# panel.net
KiCad netlist of a schematic drawn in EAGLE
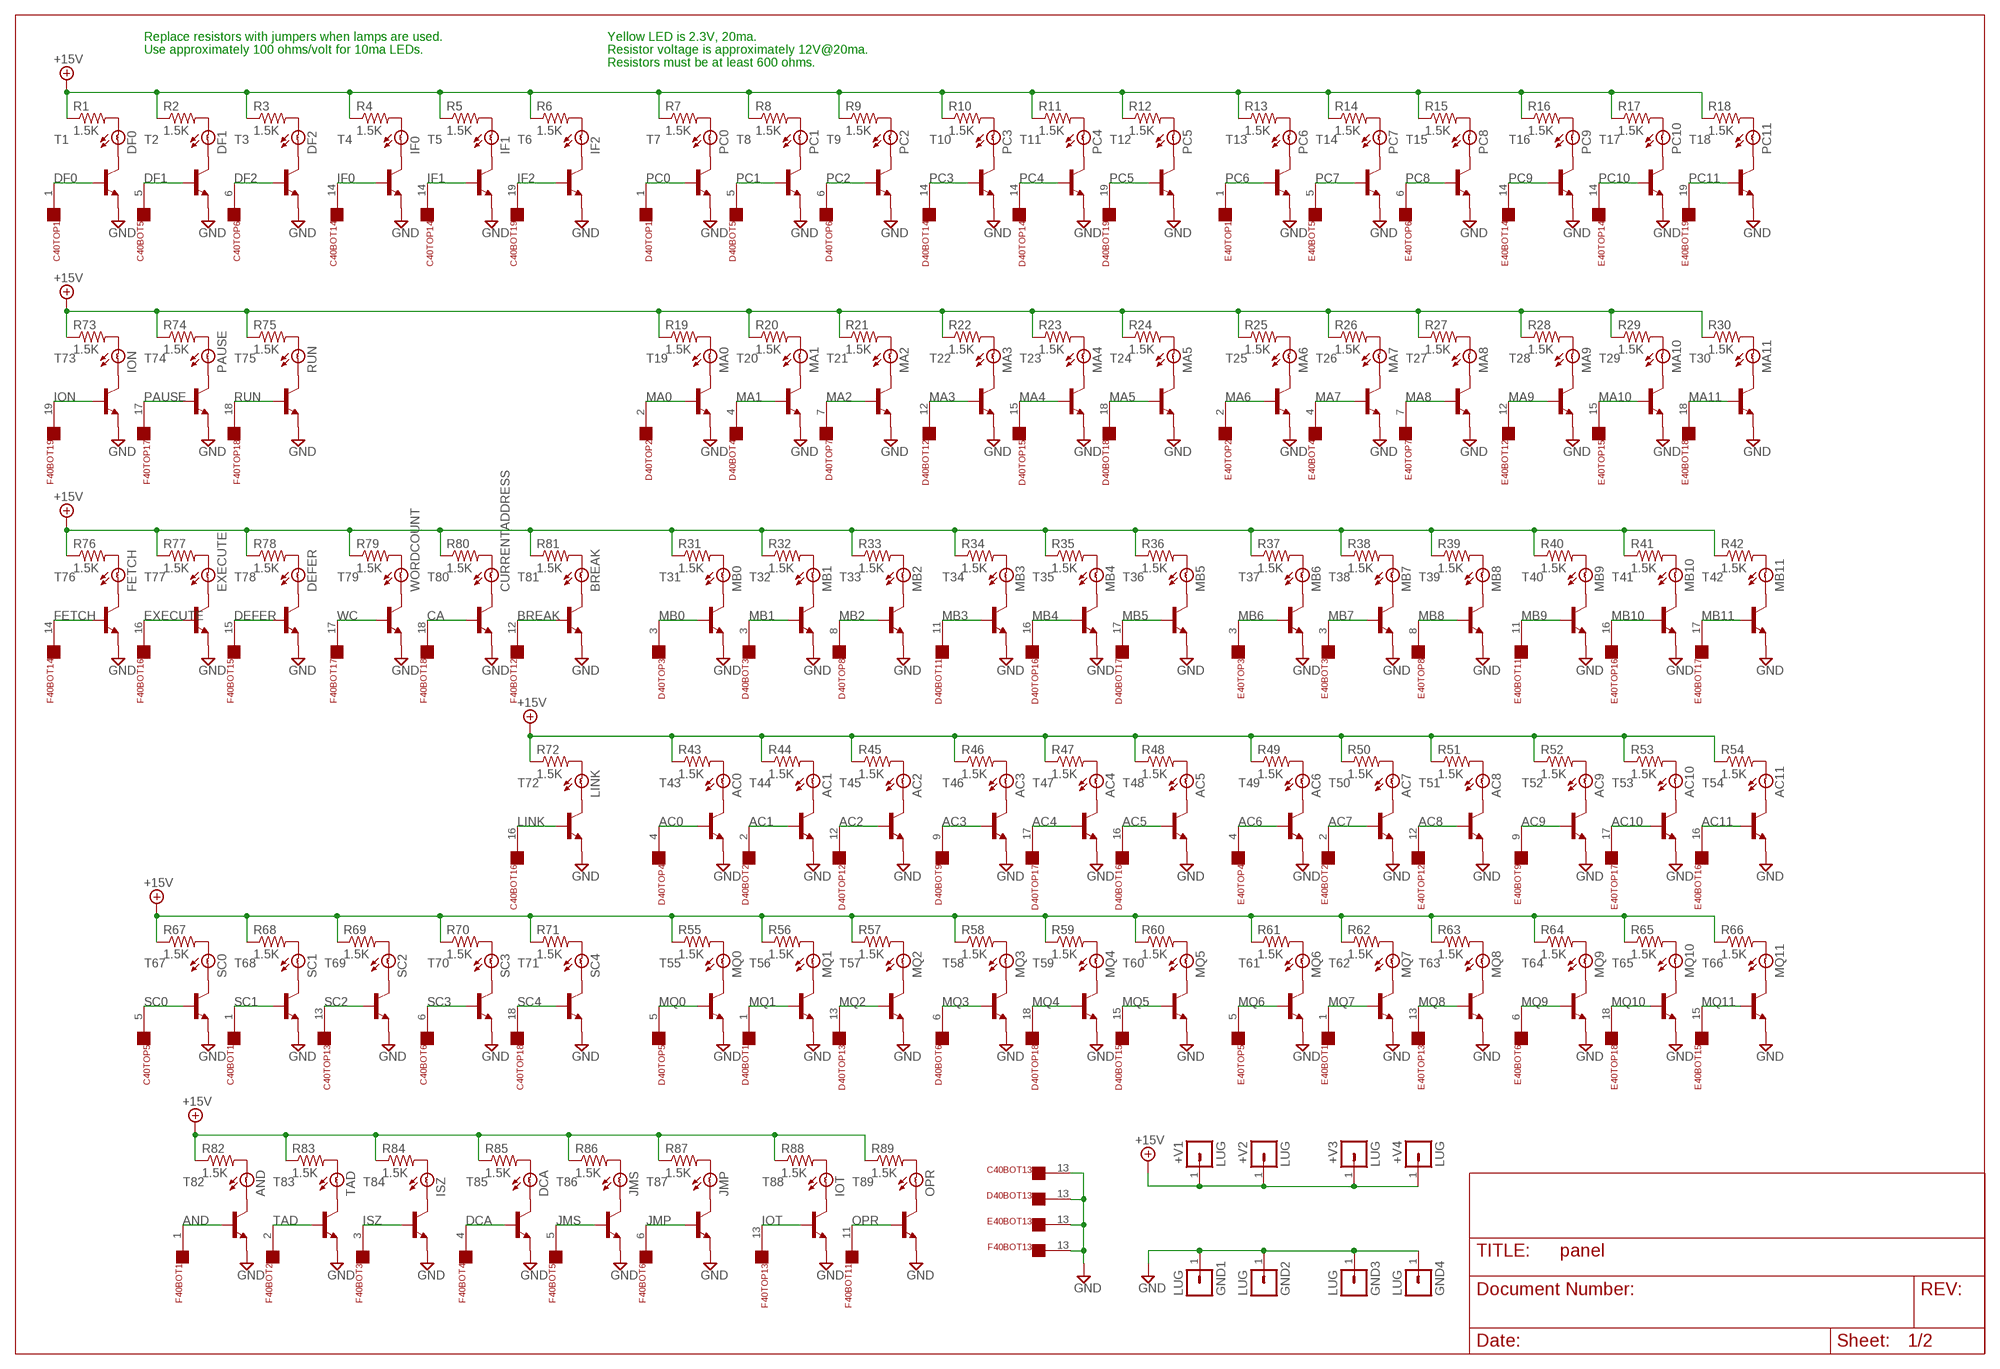
[diagram p0: schematic, sheet 1]
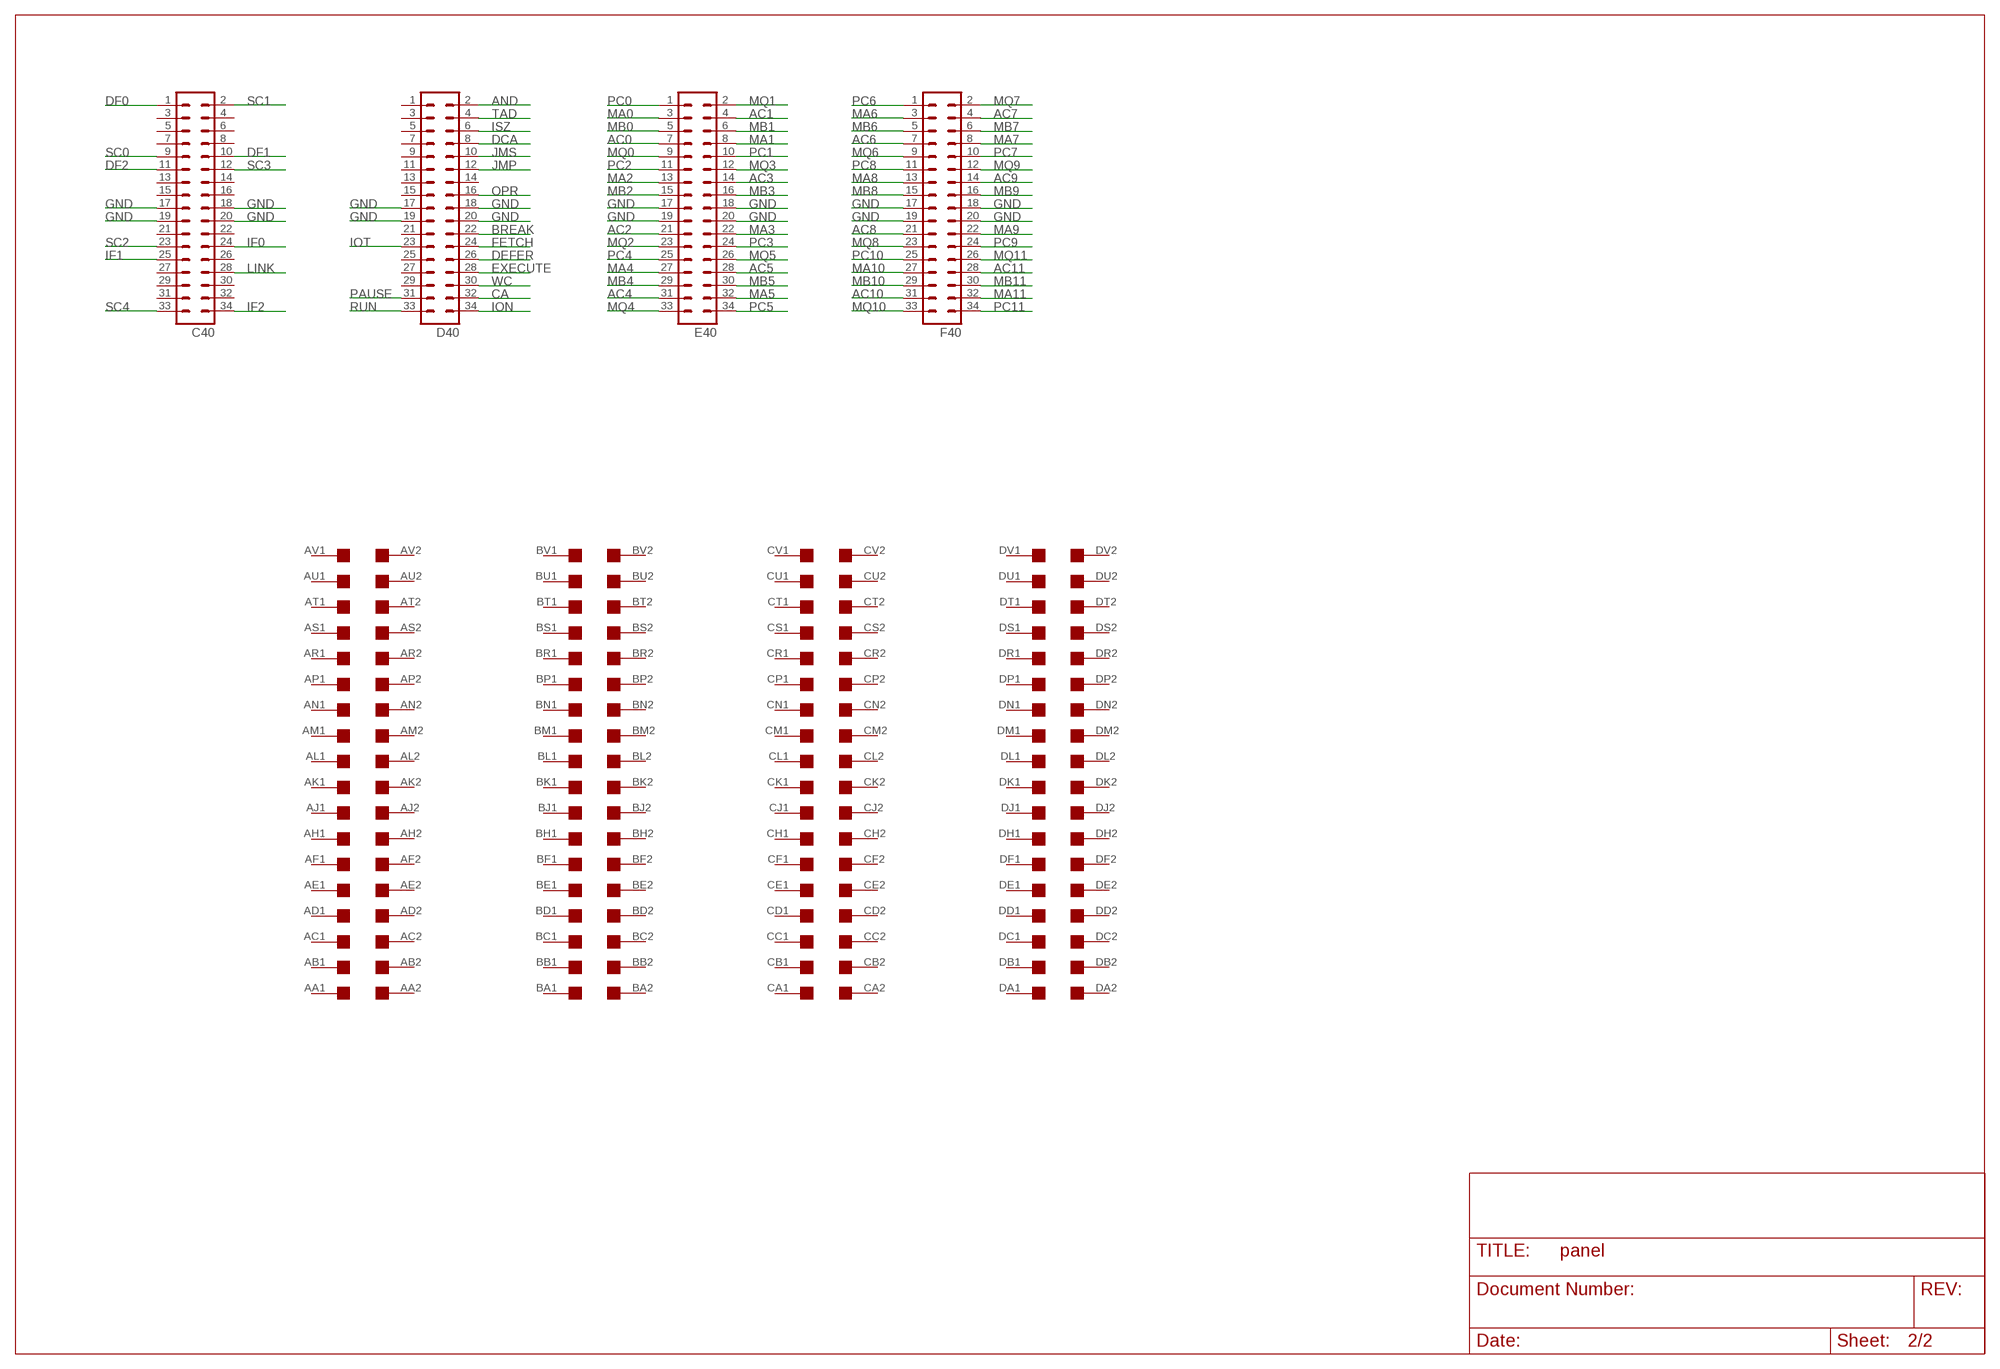
[diagram p1: schematic, sheet 2]

(export (version "E")
  (design (tool "Eeschema 10.0.6"))
  (components
    (comp (ref "+V1")
      (value "LUG")
      (footprint "eagle-import:SPADELUG")
      (libsource (lib "eagle-import") (part "LUG"))
    )
    (comp (ref "+V2")
      (value "LUG")
      (footprint "eagle-import:SPADELUG")
      (libsource (lib "eagle-import") (part "LUG"))
    )
    (comp (ref "+V3")
      (value "LUG")
      (footprint "eagle-import:SPADELUG")
      (libsource (lib "eagle-import") (part "LUG"))
    )
    (comp (ref "+V4")
      (value "LUG")
      (footprint "eagle-import:SPADELUG")
      (libsource (lib "eagle-import") (part "LUG"))
    )
    (comp (ref "AC0")
      (value "BULB")
      (footprint "eagle-import:BULB")
      (libsource (lib "eagle-import") (part "BULB"))
    )
    (comp (ref "AC1")
      (value "BULB")
      (footprint "eagle-import:BULB")
      (libsource (lib "eagle-import") (part "BULB"))
    )
    (comp (ref "AC2")
      (value "BULB")
      (footprint "eagle-import:BULB")
      (libsource (lib "eagle-import") (part "BULB"))
    )
    (comp (ref "AC3")
      (value "BULB")
      (footprint "eagle-import:BULB")
      (libsource (lib "eagle-import") (part "BULB"))
    )
    (comp (ref "AC4")
      (value "BULB")
      (footprint "eagle-import:BULB")
      (libsource (lib "eagle-import") (part "BULB"))
    )
    (comp (ref "AC5")
      (value "BULB")
      (footprint "eagle-import:BULB")
      (libsource (lib "eagle-import") (part "BULB"))
    )
    (comp (ref "AC6")
      (value "BULB")
      (footprint "eagle-import:BULB")
      (libsource (lib "eagle-import") (part "BULB"))
    )
    (comp (ref "AC7")
      (value "BULB")
      (footprint "eagle-import:BULB")
      (libsource (lib "eagle-import") (part "BULB"))
    )
    (comp (ref "AC8")
      (value "BULB")
      (footprint "eagle-import:BULB")
      (libsource (lib "eagle-import") (part "BULB"))
    )
    (comp (ref "AC9")
      (value "BULB")
      (footprint "eagle-import:BULB")
      (libsource (lib "eagle-import") (part "BULB"))
    )
    (comp (ref "AC10")
      (value "BULB")
      (footprint "eagle-import:BULB")
      (libsource (lib "eagle-import") (part "BULB"))
    )
    (comp (ref "AC11")
      (value "BULB")
      (footprint "eagle-import:BULB")
      (libsource (lib "eagle-import") (part "BULB"))
    )
    (comp (ref "AND")
      (value "BULB")
      (footprint "eagle-import:BULB")
      (libsource (lib "eagle-import") (part "BULB"))
    )
    (comp (ref "BREAK")
      (value "BULB")
      (footprint "eagle-import:BULB")
      (libsource (lib "eagle-import") (part "BULB"))
    )
    (comp (ref "C40BOT")
      (value "FLEX19")
      (footprint "eagle-import:FLEX19")
      (libsource (lib "eagle-import") (part "FLEX19"))
    )
    (comp (ref "C40TOP")
      (value "FLEX19")
      (footprint "eagle-import:FLEX19")
      (libsource (lib "eagle-import") (part "FLEX19"))
    )
    (comp (ref "CURRENTADDRESS")
      (value "BULB")
      (footprint "eagle-import:BULB")
      (libsource (lib "eagle-import") (part "BULB"))
    )
    (comp (ref "D40BOT")
      (value "FLEX19")
      (footprint "eagle-import:FLEX19")
      (libsource (lib "eagle-import") (part "FLEX19"))
    )
    (comp (ref "D40TOP")
      (value "FLEX19")
      (footprint "eagle-import:FLEX19")
      (libsource (lib "eagle-import") (part "FLEX19"))
    )
    (comp (ref "DCA")
      (value "BULB")
      (footprint "eagle-import:BULB")
      (libsource (lib "eagle-import") (part "BULB"))
    )
    (comp (ref "DEFER")
      (value "BULB")
      (footprint "eagle-import:BULB")
      (libsource (lib "eagle-import") (part "BULB"))
    )
    (comp (ref "DF0")
      (value "BULB")
      (footprint "eagle-import:BULB")
      (libsource (lib "eagle-import") (part "BULB"))
    )
    (comp (ref "DF1")
      (value "BULB")
      (footprint "eagle-import:BULB")
      (libsource (lib "eagle-import") (part "BULB"))
    )
    (comp (ref "DF2")
      (value "BULB")
      (footprint "eagle-import:BULB")
      (libsource (lib "eagle-import") (part "BULB"))
    )
    (comp (ref "E40BOT")
      (value "FLEX19")
      (footprint "eagle-import:FLEX19")
      (libsource (lib "eagle-import") (part "FLEX19"))
    )
    (comp (ref "E40TOP")
      (value "FLEX19")
      (footprint "eagle-import:FLEX19")
      (libsource (lib "eagle-import") (part "FLEX19"))
    )
    (comp (ref "EXECUTE")
      (value "BULB")
      (footprint "eagle-import:BULB")
      (libsource (lib "eagle-import") (part "BULB"))
    )
    (comp (ref "F40BOT")
      (value "FLEX19")
      (footprint "eagle-import:FLEX19")
      (libsource (lib "eagle-import") (part "FLEX19"))
    )
    (comp (ref "F40TOP")
      (value "FLEX19")
      (footprint "eagle-import:FLEX19")
      (libsource (lib "eagle-import") (part "FLEX19"))
    )
    (comp (ref "FETCH")
      (value "BULB")
      (footprint "eagle-import:BULB")
      (libsource (lib "eagle-import") (part "BULB"))
    )
    (comp (ref "GND1")
      (value "LUG")
      (footprint "eagle-import:SPADELUG")
      (libsource (lib "eagle-import") (part "LUG"))
    )
    (comp (ref "GND2")
      (value "LUG")
      (footprint "eagle-import:SPADELUG")
      (libsource (lib "eagle-import") (part "LUG"))
    )
    (comp (ref "GND3")
      (value "LUG")
      (footprint "eagle-import:SPADELUG")
      (libsource (lib "eagle-import") (part "LUG"))
    )
    (comp (ref "GND4")
      (value "LUG")
      (footprint "eagle-import:SPADELUG")
      (libsource (lib "eagle-import") (part "LUG"))
    )
    (comp (ref "IF0")
      (value "BULB")
      (footprint "eagle-import:BULB")
      (libsource (lib "eagle-import") (part "BULB"))
    )
    (comp (ref "IF1")
      (value "BULB")
      (footprint "eagle-import:BULB")
      (libsource (lib "eagle-import") (part "BULB"))
    )
    (comp (ref "IF2")
      (value "BULB")
      (footprint "eagle-import:BULB")
      (libsource (lib "eagle-import") (part "BULB"))
    )
    (comp (ref "ION")
      (value "BULB")
      (footprint "eagle-import:BULB")
      (libsource (lib "eagle-import") (part "BULB"))
    )
    (comp (ref "IOT")
      (value "BULB")
      (footprint "eagle-import:BULB")
      (libsource (lib "eagle-import") (part "BULB"))
    )
    (comp (ref "ISZ")
      (value "BULB")
      (footprint "eagle-import:BULB")
      (libsource (lib "eagle-import") (part "BULB"))
    )
    (comp (ref "JMP")
      (value "BULB")
      (footprint "eagle-import:BULB")
      (libsource (lib "eagle-import") (part "BULB"))
    )
    (comp (ref "JMS")
      (value "BULB")
      (footprint "eagle-import:BULB")
      (libsource (lib "eagle-import") (part "BULB"))
    )
    (comp (ref "LINK")
      (value "BULB")
      (footprint "eagle-import:BULB")
      (libsource (lib "eagle-import") (part "BULB"))
    )
    (comp (ref "MA0")
      (value "BULB")
      (footprint "eagle-import:BULB")
      (libsource (lib "eagle-import") (part "BULB"))
    )
    (comp (ref "MA1")
      (value "BULB")
      (footprint "eagle-import:BULB")
      (libsource (lib "eagle-import") (part "BULB"))
    )
    (comp (ref "MA2")
      (value "BULB")
      (footprint "eagle-import:BULB")
      (libsource (lib "eagle-import") (part "BULB"))
    )
    (comp (ref "MA3")
      (value "BULB")
      (footprint "eagle-import:BULB")
      (libsource (lib "eagle-import") (part "BULB"))
    )
    (comp (ref "MA4")
      (value "BULB")
      (footprint "eagle-import:BULB")
      (libsource (lib "eagle-import") (part "BULB"))
    )
    (comp (ref "MA5")
      (value "BULB")
      (footprint "eagle-import:BULB")
      (libsource (lib "eagle-import") (part "BULB"))
    )
    (comp (ref "MA6")
      (value "BULB")
      (footprint "eagle-import:BULB")
      (libsource (lib "eagle-import") (part "BULB"))
    )
    (comp (ref "MA7")
      (value "BULB")
      (footprint "eagle-import:BULB")
      (libsource (lib "eagle-import") (part "BULB"))
    )
    (comp (ref "MA8")
      (value "BULB")
      (footprint "eagle-import:BULB")
      (libsource (lib "eagle-import") (part "BULB"))
    )
    (comp (ref "MA9")
      (value "BULB")
      (footprint "eagle-import:BULB")
      (libsource (lib "eagle-import") (part "BULB"))
    )
    (comp (ref "MA10")
      (value "BULB")
      (footprint "eagle-import:BULB")
      (libsource (lib "eagle-import") (part "BULB"))
    )
    (comp (ref "MA11")
      (value "BULB")
      (footprint "eagle-import:BULB")
      (libsource (lib "eagle-import") (part "BULB"))
    )
    (comp (ref "MB0")
      (value "BULB")
      (footprint "eagle-import:BULB")
      (libsource (lib "eagle-import") (part "BULB"))
    )
    (comp (ref "MB1")
      (value "BULB")
      (footprint "eagle-import:BULB")
      (libsource (lib "eagle-import") (part "BULB"))
    )
    (comp (ref "MB2")
      (value "BULB")
      (footprint "eagle-import:BULB")
      (libsource (lib "eagle-import") (part "BULB"))
    )
    (comp (ref "MB3")
      (value "BULB")
      (footprint "eagle-import:BULB")
      (libsource (lib "eagle-import") (part "BULB"))
    )
    (comp (ref "MB4")
      (value "BULB")
      (footprint "eagle-import:BULB")
      (libsource (lib "eagle-import") (part "BULB"))
    )
    (comp (ref "MB5")
      (value "BULB")
      (footprint "eagle-import:BULB")
      (libsource (lib "eagle-import") (part "BULB"))
    )
    (comp (ref "MB6")
      (value "BULB")
      (footprint "eagle-import:BULB")
      (libsource (lib "eagle-import") (part "BULB"))
    )
    (comp (ref "MB7")
      (value "BULB")
      (footprint "eagle-import:BULB")
      (libsource (lib "eagle-import") (part "BULB"))
    )
    (comp (ref "MB8")
      (value "BULB")
      (footprint "eagle-import:BULB")
      (libsource (lib "eagle-import") (part "BULB"))
    )
    (comp (ref "MB9")
      (value "BULB")
      (footprint "eagle-import:BULB")
      (libsource (lib "eagle-import") (part "BULB"))
    )
    (comp (ref "MB10")
      (value "BULB")
      (footprint "eagle-import:BULB")
      (libsource (lib "eagle-import") (part "BULB"))
    )
    (comp (ref "MB11")
      (value "BULB")
      (footprint "eagle-import:BULB")
      (libsource (lib "eagle-import") (part "BULB"))
    )
    (comp (ref "MQ0")
      (value "BULB")
      (footprint "eagle-import:BULB")
      (libsource (lib "eagle-import") (part "BULB"))
    )
    (comp (ref "MQ1")
      (value "BULB")
      (footprint "eagle-import:BULB")
      (libsource (lib "eagle-import") (part "BULB"))
    )
    (comp (ref "MQ2")
      (value "BULB")
      (footprint "eagle-import:BULB")
      (libsource (lib "eagle-import") (part "BULB"))
    )
    (comp (ref "MQ3")
      (value "BULB")
      (footprint "eagle-import:BULB")
      (libsource (lib "eagle-import") (part "BULB"))
    )
    (comp (ref "MQ4")
      (value "BULB")
      (footprint "eagle-import:BULB")
      (libsource (lib "eagle-import") (part "BULB"))
    )
    (comp (ref "MQ5")
      (value "BULB")
      (footprint "eagle-import:BULB")
      (libsource (lib "eagle-import") (part "BULB"))
    )
    (comp (ref "MQ6")
      (value "BULB")
      (footprint "eagle-import:BULB")
      (libsource (lib "eagle-import") (part "BULB"))
    )
    (comp (ref "MQ7")
      (value "BULB")
      (footprint "eagle-import:BULB")
      (libsource (lib "eagle-import") (part "BULB"))
    )
    (comp (ref "MQ8")
      (value "BULB")
      (footprint "eagle-import:BULB")
      (libsource (lib "eagle-import") (part "BULB"))
    )
    (comp (ref "MQ9")
      (value "BULB")
      (footprint "eagle-import:BULB")
      (libsource (lib "eagle-import") (part "BULB"))
    )
    (comp (ref "MQ10")
      (value "BULB")
      (footprint "eagle-import:BULB")
      (libsource (lib "eagle-import") (part "BULB"))
    )
    (comp (ref "MQ11")
      (value "BULB")
      (footprint "eagle-import:BULB")
      (libsource (lib "eagle-import") (part "BULB"))
    )
    (comp (ref "OPR")
      (value "BULB")
      (footprint "eagle-import:BULB")
      (libsource (lib "eagle-import") (part "BULB"))
    )
    (comp (ref "PAUSE")
      (value "BULB")
      (footprint "eagle-import:BULB")
      (libsource (lib "eagle-import") (part "BULB"))
    )
    (comp (ref "PC0")
      (value "BULB")
      (footprint "eagle-import:BULB")
      (libsource (lib "eagle-import") (part "BULB"))
    )
    (comp (ref "PC1")
      (value "BULB")
      (footprint "eagle-import:BULB")
      (libsource (lib "eagle-import") (part "BULB"))
    )
    (comp (ref "PC2")
      (value "BULB")
      (footprint "eagle-import:BULB")
      (libsource (lib "eagle-import") (part "BULB"))
    )
    (comp (ref "PC3")
      (value "BULB")
      (footprint "eagle-import:BULB")
      (libsource (lib "eagle-import") (part "BULB"))
    )
    (comp (ref "PC4")
      (value "BULB")
      (footprint "eagle-import:BULB")
      (libsource (lib "eagle-import") (part "BULB"))
    )
    (comp (ref "PC5")
      (value "BULB")
      (footprint "eagle-import:BULB")
      (libsource (lib "eagle-import") (part "BULB"))
    )
    (comp (ref "PC6")
      (value "BULB")
      (footprint "eagle-import:BULB")
      (libsource (lib "eagle-import") (part "BULB"))
    )
    (comp (ref "PC7")
      (value "BULB")
      (footprint "eagle-import:BULB")
      (libsource (lib "eagle-import") (part "BULB"))
    )
    (comp (ref "PC8")
      (value "BULB")
      (footprint "eagle-import:BULB")
      (libsource (lib "eagle-import") (part "BULB"))
    )
    (comp (ref "PC9")
      (value "BULB")
      (footprint "eagle-import:BULB")
      (libsource (lib "eagle-import") (part "BULB"))
    )
    (comp (ref "PC10")
      (value "BULB")
      (footprint "eagle-import:BULB")
      (libsource (lib "eagle-import") (part "BULB"))
    )
    (comp (ref "PC11")
      (value "BULB")
      (footprint "eagle-import:BULB")
      (libsource (lib "eagle-import") (part "BULB"))
    )
    (comp (ref "R1")
      (value "1.5K")
      (footprint "eagle-import:0207_10")
      (libsource (lib "eagle-import") (part "R-US_0207/10"))
    )
    (comp (ref "R2")
      (value "1.5K")
      (footprint "eagle-import:0207_10")
      (libsource (lib "eagle-import") (part "R-US_0207/10"))
    )
    (comp (ref "R3")
      (value "1.5K")
      (footprint "eagle-import:0207_10")
      (libsource (lib "eagle-import") (part "R-US_0207/10"))
    )
    (comp (ref "R4")
      (value "1.5K")
      (footprint "eagle-import:0207_10")
      (libsource (lib "eagle-import") (part "R-US_0207/10"))
    )
    (comp (ref "R5")
      (value "1.5K")
      (footprint "eagle-import:0207_10")
      (libsource (lib "eagle-import") (part "R-US_0207/10"))
    )
    (comp (ref "R6")
      (value "1.5K")
      (footprint "eagle-import:0207_10")
      (libsource (lib "eagle-import") (part "R-US_0207/10"))
    )
    (comp (ref "R7")
      (value "1.5K")
      (footprint "eagle-import:0207_10")
      (libsource (lib "eagle-import") (part "R-US_0207/10"))
    )
    (comp (ref "R8")
      (value "1.5K")
      (footprint "eagle-import:0207_10")
      (libsource (lib "eagle-import") (part "R-US_0207/10"))
    )
    (comp (ref "R9")
      (value "1.5K")
      (footprint "eagle-import:0207_10")
      (libsource (lib "eagle-import") (part "R-US_0207/10"))
    )
    (comp (ref "R10")
      (value "1.5K")
      (footprint "eagle-import:0207_10")
      (libsource (lib "eagle-import") (part "R-US_0207/10"))
    )
    (comp (ref "R11")
      (value "1.5K")
      (footprint "eagle-import:0207_10")
      (libsource (lib "eagle-import") (part "R-US_0207/10"))
    )
    (comp (ref "R12")
      (value "1.5K")
      (footprint "eagle-import:0207_10")
      (libsource (lib "eagle-import") (part "R-US_0207/10"))
    )
    (comp (ref "R13")
      (value "1.5K")
      (footprint "eagle-import:0207_10")
      (libsource (lib "eagle-import") (part "R-US_0207/10"))
    )
    (comp (ref "R14")
      (value "1.5K")
      (footprint "eagle-import:0207_10")
      (libsource (lib "eagle-import") (part "R-US_0207/10"))
    )
    (comp (ref "R15")
      (value "1.5K")
      (footprint "eagle-import:0207_10")
      (libsource (lib "eagle-import") (part "R-US_0207/10"))
    )
    (comp (ref "R16")
      (value "1.5K")
      (footprint "eagle-import:0207_10")
      (libsource (lib "eagle-import") (part "R-US_0207/10"))
    )
    (comp (ref "R17")
      (value "1.5K")
      (footprint "eagle-import:0207_10")
      (libsource (lib "eagle-import") (part "R-US_0207/10"))
    )
    (comp (ref "R18")
      (value "1.5K")
      (footprint "eagle-import:0207_10")
      (libsource (lib "eagle-import") (part "R-US_0207/10"))
    )
    (comp (ref "R19")
      (value "1.5K")
      (footprint "eagle-import:0207_10")
      (libsource (lib "eagle-import") (part "R-US_0207/10"))
    )
    (comp (ref "R20")
      (value "1.5K")
      (footprint "eagle-import:0207_10")
      (libsource (lib "eagle-import") (part "R-US_0207/10"))
    )
    (comp (ref "R21")
      (value "1.5K")
      (footprint "eagle-import:0207_10")
      (libsource (lib "eagle-import") (part "R-US_0207/10"))
    )
    (comp (ref "R22")
      (value "1.5K")
      (footprint "eagle-import:0207_10")
      (libsource (lib "eagle-import") (part "R-US_0207/10"))
    )
    (comp (ref "R23")
      (value "1.5K")
      (footprint "eagle-import:0207_10")
      (libsource (lib "eagle-import") (part "R-US_0207/10"))
    )
    (comp (ref "R24")
      (value "1.5K")
      (footprint "eagle-import:0207_10")
      (libsource (lib "eagle-import") (part "R-US_0207/10"))
    )
    (comp (ref "R25")
      (value "1.5K")
      (footprint "eagle-import:0207_10")
      (libsource (lib "eagle-import") (part "R-US_0207/10"))
    )
    (comp (ref "R26")
      (value "1.5K")
      (footprint "eagle-import:0207_10")
      (libsource (lib "eagle-import") (part "R-US_0207/10"))
    )
    (comp (ref "R27")
      (value "1.5K")
      (footprint "eagle-import:0207_10")
      (libsource (lib "eagle-import") (part "R-US_0207/10"))
    )
    (comp (ref "R28")
      (value "1.5K")
      (footprint "eagle-import:0207_10")
      (libsource (lib "eagle-import") (part "R-US_0207/10"))
    )
    (comp (ref "R29")
      (value "1.5K")
      (footprint "eagle-import:0207_10")
      (libsource (lib "eagle-import") (part "R-US_0207/10"))
    )
    (comp (ref "R30")
      (value "1.5K")
      (footprint "eagle-import:0207_10")
      (libsource (lib "eagle-import") (part "R-US_0207/10"))
    )
    (comp (ref "R31")
      (value "1.5K")
      (footprint "eagle-import:0207_10")
      (libsource (lib "eagle-import") (part "R-US_0207/10"))
    )
    (comp (ref "R32")
      (value "1.5K")
      (footprint "eagle-import:0207_10")
      (libsource (lib "eagle-import") (part "R-US_0207/10"))
    )
    (comp (ref "R33")
      (value "1.5K")
      (footprint "eagle-import:0207_10")
      (libsource (lib "eagle-import") (part "R-US_0207/10"))
    )
    (comp (ref "R34")
      (value "1.5K")
      (footprint "eagle-import:0207_10")
      (libsource (lib "eagle-import") (part "R-US_0207/10"))
    )
    (comp (ref "R35")
      (value "1.5K")
      (footprint "eagle-import:0207_10")
      (libsource (lib "eagle-import") (part "R-US_0207/10"))
    )
    (comp (ref "R36")
      (value "1.5K")
      (footprint "eagle-import:0207_10")
      (libsource (lib "eagle-import") (part "R-US_0207/10"))
    )
    (comp (ref "R37")
      (value "1.5K")
      (footprint "eagle-import:0207_10")
      (libsource (lib "eagle-import") (part "R-US_0207/10"))
    )
    (comp (ref "R38")
      (value "1.5K")
      (footprint "eagle-import:0207_10")
      (libsource (lib "eagle-import") (part "R-US_0207/10"))
    )
    (comp (ref "R39")
      (value "1.5K")
      (footprint "eagle-import:0207_10")
      (libsource (lib "eagle-import") (part "R-US_0207/10"))
    )
    (comp (ref "R40")
      (value "1.5K")
      (footprint "eagle-import:0207_10")
      (libsource (lib "eagle-import") (part "R-US_0207/10"))
    )
    (comp (ref "R41")
      (value "1.5K")
      (footprint "eagle-import:0207_10")
      (libsource (lib "eagle-import") (part "R-US_0207/10"))
    )
    (comp (ref "R42")
      (value "1.5K")
      (footprint "eagle-import:0207_10")
      (libsource (lib "eagle-import") (part "R-US_0207/10"))
    )
    (comp (ref "R43")
      (value "1.5K")
      (footprint "eagle-import:0207_10")
      (libsource (lib "eagle-import") (part "R-US_0207/10"))
    )
    (comp (ref "R44")
      (value "1.5K")
      (footprint "eagle-import:0207_10")
      (libsource (lib "eagle-import") (part "R-US_0207/10"))
    )
    (comp (ref "R45")
      (value "1.5K")
      (footprint "eagle-import:0207_10")
      (libsource (lib "eagle-import") (part "R-US_0207/10"))
    )
    (comp (ref "R46")
      (value "1.5K")
      (footprint "eagle-import:0207_10")
      (libsource (lib "eagle-import") (part "R-US_0207/10"))
    )
    (comp (ref "R47")
      (value "1.5K")
      (footprint "eagle-import:0207_10")
      (libsource (lib "eagle-import") (part "R-US_0207/10"))
    )
    (comp (ref "R48")
      (value "1.5K")
      (footprint "eagle-import:0207_10")
      (libsource (lib "eagle-import") (part "R-US_0207/10"))
    )
    (comp (ref "R49")
      (value "1.5K")
      (footprint "eagle-import:0207_10")
      (libsource (lib "eagle-import") (part "R-US_0207/10"))
    )
    (comp (ref "R50")
      (value "1.5K")
      (footprint "eagle-import:0207_10")
      (libsource (lib "eagle-import") (part "R-US_0207/10"))
    )
    (comp (ref "R51")
      (value "1.5K")
      (footprint "eagle-import:0207_10")
      (libsource (lib "eagle-import") (part "R-US_0207/10"))
    )
    (comp (ref "R52")
      (value "1.5K")
      (footprint "eagle-import:0207_10")
      (libsource (lib "eagle-import") (part "R-US_0207/10"))
    )
    (comp (ref "R53")
      (value "1.5K")
      (footprint "eagle-import:0207_10")
      (libsource (lib "eagle-import") (part "R-US_0207/10"))
    )
    (comp (ref "R54")
      (value "1.5K")
      (footprint "eagle-import:0207_10")
      (libsource (lib "eagle-import") (part "R-US_0207/10"))
    )
    (comp (ref "R55")
      (value "1.5K")
      (footprint "eagle-import:0207_10")
      (libsource (lib "eagle-import") (part "R-US_0207/10"))
    )
    (comp (ref "R56")
      (value "1.5K")
      (footprint "eagle-import:0207_10")
      (libsource (lib "eagle-import") (part "R-US_0207/10"))
    )
    (comp (ref "R57")
      (value "1.5K")
      (footprint "eagle-import:0207_10")
      (libsource (lib "eagle-import") (part "R-US_0207/10"))
    )
    (comp (ref "R58")
      (value "1.5K")
      (footprint "eagle-import:0207_10")
      (libsource (lib "eagle-import") (part "R-US_0207/10"))
    )
    (comp (ref "R59")
      (value "1.5K")
      (footprint "eagle-import:0207_10")
      (libsource (lib "eagle-import") (part "R-US_0207/10"))
    )
    (comp (ref "R60")
      (value "1.5K")
      (footprint "eagle-import:0207_10")
      (libsource (lib "eagle-import") (part "R-US_0207/10"))
    )
    (comp (ref "R61")
      (value "1.5K")
      (footprint "eagle-import:0207_10")
      (libsource (lib "eagle-import") (part "R-US_0207/10"))
    )
    (comp (ref "R62")
      (value "1.5K")
      (footprint "eagle-import:0207_10")
      (libsource (lib "eagle-import") (part "R-US_0207/10"))
    )
    (comp (ref "R63")
      (value "1.5K")
      (footprint "eagle-import:0207_10")
      (libsource (lib "eagle-import") (part "R-US_0207/10"))
    )
    (comp (ref "R64")
      (value "1.5K")
      (footprint "eagle-import:0207_10")
      (libsource (lib "eagle-import") (part "R-US_0207/10"))
    )
    (comp (ref "R65")
      (value "1.5K")
      (footprint "eagle-import:0207_10")
      (libsource (lib "eagle-import") (part "R-US_0207/10"))
    )
    (comp (ref "R66")
      (value "1.5K")
      (footprint "eagle-import:0207_10")
      (libsource (lib "eagle-import") (part "R-US_0207/10"))
    )
    (comp (ref "R67")
      (value "1.5K")
      (footprint "eagle-import:0207_10")
      (libsource (lib "eagle-import") (part "R-US_0207/10"))
    )
    (comp (ref "R68")
      (value "1.5K")
      (footprint "eagle-import:0207_10")
      (libsource (lib "eagle-import") (part "R-US_0207/10"))
    )
    (comp (ref "R69")
      (value "1.5K")
      (footprint "eagle-import:0207_10")
      (libsource (lib "eagle-import") (part "R-US_0207/10"))
    )
    (comp (ref "R70")
      (value "1.5K")
      (footprint "eagle-import:0207_10")
      (libsource (lib "eagle-import") (part "R-US_0207/10"))
    )
    (comp (ref "R71")
      (value "1.5K")
      (footprint "eagle-import:0207_10")
      (libsource (lib "eagle-import") (part "R-US_0207/10"))
    )
    (comp (ref "R72")
      (value "1.5K")
      (footprint "eagle-import:0207_10")
      (libsource (lib "eagle-import") (part "R-US_0207/10"))
    )
    (comp (ref "R73")
      (value "1.5K")
      (footprint "eagle-import:0207_10")
      (libsource (lib "eagle-import") (part "R-US_0207/10"))
    )
    (comp (ref "R74")
      (value "1.5K")
      (footprint "eagle-import:0207_10")
      (libsource (lib "eagle-import") (part "R-US_0207/10"))
    )
    (comp (ref "R75")
      (value "1.5K")
      (footprint "eagle-import:0207_10")
      (libsource (lib "eagle-import") (part "R-US_0207/10"))
    )
    (comp (ref "R76")
      (value "1.5K")
      (footprint "eagle-import:0207_10")
      (libsource (lib "eagle-import") (part "R-US_0207/10"))
    )
    (comp (ref "R77")
      (value "1.5K")
      (footprint "eagle-import:0207_10")
      (libsource (lib "eagle-import") (part "R-US_0207/10"))
    )
    (comp (ref "R78")
      (value "1.5K")
      (footprint "eagle-import:0207_10")
      (libsource (lib "eagle-import") (part "R-US_0207/10"))
    )
    (comp (ref "R79")
      (value "1.5K")
      (footprint "eagle-import:0207_10")
      (libsource (lib "eagle-import") (part "R-US_0207/10"))
    )
    (comp (ref "R80")
      (value "1.5K")
      (footprint "eagle-import:0207_10")
      (libsource (lib "eagle-import") (part "R-US_0207/10"))
    )
    (comp (ref "R81")
      (value "1.5K")
      (footprint "eagle-import:0207_10")
      (libsource (lib "eagle-import") (part "R-US_0207/10"))
    )
    (comp (ref "R82")
      (value "1.5K")
      (footprint "eagle-import:0207_10")
      (libsource (lib "eagle-import") (part "R-US_0207/10"))
    )
    (comp (ref "R83")
      (value "1.5K")
      (footprint "eagle-import:0207_10")
      (libsource (lib "eagle-import") (part "R-US_0207/10"))
    )
    (comp (ref "R84")
      (value "1.5K")
      (footprint "eagle-import:0207_10")
      (libsource (lib "eagle-import") (part "R-US_0207/10"))
    )
    (comp (ref "R85")
      (value "1.5K")
      (footprint "eagle-import:0207_10")
      (libsource (lib "eagle-import") (part "R-US_0207/10"))
    )
    (comp (ref "R86")
      (value "1.5K")
      (footprint "eagle-import:0207_10")
      (libsource (lib "eagle-import") (part "R-US_0207/10"))
    )
    (comp (ref "R87")
      (value "1.5K")
      (footprint "eagle-import:0207_10")
      (libsource (lib "eagle-import") (part "R-US_0207/10"))
    )
    (comp (ref "R88")
      (value "1.5K")
      (footprint "eagle-import:0207_10")
      (libsource (lib "eagle-import") (part "R-US_0207/10"))
    )
    (comp (ref "R89")
      (value "1.5K")
      (footprint "eagle-import:0207_10")
      (libsource (lib "eagle-import") (part "R-US_0207/10"))
    )
    (comp (ref "RUN")
      (value "BULB")
      (footprint "eagle-import:BULB")
      (libsource (lib "eagle-import") (part "BULB"))
    )
    (comp (ref "SC0")
      (value "BULB")
      (footprint "eagle-import:BULB")
      (libsource (lib "eagle-import") (part "BULB"))
    )
    (comp (ref "SC1")
      (value "BULB")
      (footprint "eagle-import:BULB")
      (libsource (lib "eagle-import") (part "BULB"))
    )
    (comp (ref "SC2")
      (value "BULB")
      (footprint "eagle-import:BULB")
      (libsource (lib "eagle-import") (part "BULB"))
    )
    (comp (ref "SC3")
      (value "BULB")
      (footprint "eagle-import:BULB")
      (libsource (lib "eagle-import") (part "BULB"))
    )
    (comp (ref "SC4")
      (value "BULB")
      (footprint "eagle-import:BULB")
      (libsource (lib "eagle-import") (part "BULB"))
    )
    (comp (ref "T1")
      (value "MPS2222A-NPN-TO92-CBE")
      (footprint "eagle-import:TO92-CBE")
      (libsource (lib "eagle-import") (part "-NPN-TO92-CBEMPS2222A"))
    )
    (comp (ref "T2")
      (value "MPS2222A-NPN-TO92-CBE")
      (footprint "eagle-import:TO92-CBE")
      (libsource (lib "eagle-import") (part "-NPN-TO92-CBEMPS2222A"))
    )
    (comp (ref "T3")
      (value "MPS2222A-NPN-TO92-CBE")
      (footprint "eagle-import:TO92-CBE")
      (libsource (lib "eagle-import") (part "-NPN-TO92-CBEMPS2222A"))
    )
    (comp (ref "T4")
      (value "MPS2222A-NPN-TO92-CBE")
      (footprint "eagle-import:TO92-CBE")
      (libsource (lib "eagle-import") (part "-NPN-TO92-CBEMPS2222A"))
    )
    (comp (ref "T5")
      (value "MPS2222A-NPN-TO92-CBE")
      (footprint "eagle-import:TO92-CBE")
      (libsource (lib "eagle-import") (part "-NPN-TO92-CBEMPS2222A"))
    )
    (comp (ref "T6")
      (value "MPS2222A-NPN-TO92-CBE")
      (footprint "eagle-import:TO92-CBE")
      (libsource (lib "eagle-import") (part "-NPN-TO92-CBEMPS2222A"))
    )
    (comp (ref "T7")
      (value "MPS2222A-NPN-TO92-CBE")
      (footprint "eagle-import:TO92-CBE")
      (libsource (lib "eagle-import") (part "-NPN-TO92-CBEMPS2222A"))
    )
    (comp (ref "T8")
      (value "MPS2222A-NPN-TO92-CBE")
      (footprint "eagle-import:TO92-CBE")
      (libsource (lib "eagle-import") (part "-NPN-TO92-CBEMPS2222A"))
    )
    (comp (ref "T9")
      (value "MPS2222A-NPN-TO92-CBE")
      (footprint "eagle-import:TO92-CBE")
      (libsource (lib "eagle-import") (part "-NPN-TO92-CBEMPS2222A"))
    )
    (comp (ref "T10")
      (value "MPS2222A-NPN-TO92-CBE")
      (footprint "eagle-import:TO92-CBE")
      (libsource (lib "eagle-import") (part "-NPN-TO92-CBEMPS2222A"))
    )
    (comp (ref "T11")
      (value "MPS2222A-NPN-TO92-CBE")
      (footprint "eagle-import:TO92-CBE")
      (libsource (lib "eagle-import") (part "-NPN-TO92-CBEMPS2222A"))
    )
    (comp (ref "T12")
      (value "MPS2222A-NPN-TO92-CBE")
      (footprint "eagle-import:TO92-CBE")
      (libsource (lib "eagle-import") (part "-NPN-TO92-CBEMPS2222A"))
    )
    (comp (ref "T13")
      (value "MPS2222A-NPN-TO92-CBE")
      (footprint "eagle-import:TO92-CBE")
      (libsource (lib "eagle-import") (part "-NPN-TO92-CBEMPS2222A"))
    )
    (comp (ref "T14")
      (value "MPS2222A-NPN-TO92-CBE")
      (footprint "eagle-import:TO92-CBE")
      (libsource (lib "eagle-import") (part "-NPN-TO92-CBEMPS2222A"))
    )
    (comp (ref "T15")
      (value "MPS2222A-NPN-TO92-CBE")
      (footprint "eagle-import:TO92-CBE")
      (libsource (lib "eagle-import") (part "-NPN-TO92-CBEMPS2222A"))
    )
    (comp (ref "T16")
      (value "MPS2222A-NPN-TO92-CBE")
      (footprint "eagle-import:TO92-CBE")
      (libsource (lib "eagle-import") (part "-NPN-TO92-CBEMPS2222A"))
    )
    (comp (ref "T17")
      (value "MPS2222A-NPN-TO92-CBE")
      (footprint "eagle-import:TO92-CBE")
      (libsource (lib "eagle-import") (part "-NPN-TO92-CBEMPS2222A"))
    )
    (comp (ref "T18")
      (value "MPS2222A-NPN-TO92-CBE")
      (footprint "eagle-import:TO92-CBE")
      (libsource (lib "eagle-import") (part "-NPN-TO92-CBEMPS2222A"))
    )
    (comp (ref "T19")
      (value "MPS2222A-NPN-TO92-CBE")
      (footprint "eagle-import:TO92-CBE")
      (libsource (lib "eagle-import") (part "-NPN-TO92-CBEMPS2222A"))
    )
    (comp (ref "T20")
      (value "MPS2222A-NPN-TO92-CBE")
      (footprint "eagle-import:TO92-CBE")
      (libsource (lib "eagle-import") (part "-NPN-TO92-CBEMPS2222A"))
    )
    (comp (ref "T21")
      (value "MPS2222A-NPN-TO92-CBE")
      (footprint "eagle-import:TO92-CBE")
      (libsource (lib "eagle-import") (part "-NPN-TO92-CBEMPS2222A"))
    )
    (comp (ref "T22")
      (value "MPS2222A-NPN-TO92-CBE")
      (footprint "eagle-import:TO92-CBE")
      (libsource (lib "eagle-import") (part "-NPN-TO92-CBEMPS2222A"))
    )
    (comp (ref "T23")
      (value "MPS2222A-NPN-TO92-CBE")
      (footprint "eagle-import:TO92-CBE")
      (libsource (lib "eagle-import") (part "-NPN-TO92-CBEMPS2222A"))
    )
    (comp (ref "T24")
      (value "MPS2222A-NPN-TO92-CBE")
      (footprint "eagle-import:TO92-CBE")
      (libsource (lib "eagle-import") (part "-NPN-TO92-CBEMPS2222A"))
    )
    (comp (ref "T25")
      (value "MPS2222A-NPN-TO92-CBE")
      (footprint "eagle-import:TO92-CBE")
      (libsource (lib "eagle-import") (part "-NPN-TO92-CBEMPS2222A"))
    )
    (comp (ref "T26")
      (value "MPS2222A-NPN-TO92-CBE")
      (footprint "eagle-import:TO92-CBE")
      (libsource (lib "eagle-import") (part "-NPN-TO92-CBEMPS2222A"))
    )
    (comp (ref "T27")
      (value "MPS2222A-NPN-TO92-CBE")
      (footprint "eagle-import:TO92-CBE")
      (libsource (lib "eagle-import") (part "-NPN-TO92-CBEMPS2222A"))
    )
    (comp (ref "T28")
      (value "MPS2222A-NPN-TO92-CBE")
      (footprint "eagle-import:TO92-CBE")
      (libsource (lib "eagle-import") (part "-NPN-TO92-CBEMPS2222A"))
    )
    (comp (ref "T29")
      (value "MPS2222A-NPN-TO92-CBE")
      (footprint "eagle-import:TO92-CBE")
      (libsource (lib "eagle-import") (part "-NPN-TO92-CBEMPS2222A"))
    )
    (comp (ref "T30")
      (value "MPS2222A-NPN-TO92-CBE")
      (footprint "eagle-import:TO92-CBE")
      (libsource (lib "eagle-import") (part "-NPN-TO92-CBEMPS2222A"))
    )
    (comp (ref "T31")
      (value "MPS2222A-NPN-TO92-CBE")
      (footprint "eagle-import:TO92-CBE")
      (libsource (lib "eagle-import") (part "-NPN-TO92-CBEMPS2222A"))
    )
    (comp (ref "T32")
      (value "MPS2222A-NPN-TO92-CBE")
      (footprint "eagle-import:TO92-CBE")
      (libsource (lib "eagle-import") (part "-NPN-TO92-CBEMPS2222A"))
    )
    (comp (ref "T33")
      (value "MPS2222A-NPN-TO92-CBE")
      (footprint "eagle-import:TO92-CBE")
      (libsource (lib "eagle-import") (part "-NPN-TO92-CBEMPS2222A"))
    )
    (comp (ref "T34")
      (value "MPS2222A-NPN-TO92-CBE")
      (footprint "eagle-import:TO92-CBE")
      (libsource (lib "eagle-import") (part "-NPN-TO92-CBEMPS2222A"))
    )
    (comp (ref "T35")
      (value "MPS2222A-NPN-TO92-CBE")
      (footprint "eagle-import:TO92-CBE")
      (libsource (lib "eagle-import") (part "-NPN-TO92-CBEMPS2222A"))
    )
    (comp (ref "T36")
      (value "MPS2222A-NPN-TO92-CBE")
      (footprint "eagle-import:TO92-CBE")
      (libsource (lib "eagle-import") (part "-NPN-TO92-CBEMPS2222A"))
    )
    (comp (ref "T37")
      (value "MPS2222A-NPN-TO92-CBE")
      (footprint "eagle-import:TO92-CBE")
      (libsource (lib "eagle-import") (part "-NPN-TO92-CBEMPS2222A"))
    )
    (comp (ref "T38")
      (value "MPS2222A-NPN-TO92-CBE")
      (footprint "eagle-import:TO92-CBE")
      (libsource (lib "eagle-import") (part "-NPN-TO92-CBEMPS2222A"))
    )
    (comp (ref "T39")
      (value "MPS2222A-NPN-TO92-CBE")
      (footprint "eagle-import:TO92-CBE")
      (libsource (lib "eagle-import") (part "-NPN-TO92-CBEMPS2222A"))
    )
    (comp (ref "T40")
      (value "MPS2222A-NPN-TO92-CBE")
      (footprint "eagle-import:TO92-CBE")
      (libsource (lib "eagle-import") (part "-NPN-TO92-CBEMPS2222A"))
    )
    (comp (ref "T41")
      (value "MPS2222A-NPN-TO92-CBE")
      (footprint "eagle-import:TO92-CBE")
      (libsource (lib "eagle-import") (part "-NPN-TO92-CBEMPS2222A"))
    )
    (comp (ref "T42")
      (value "MPS2222A-NPN-TO92-CBE")
      (footprint "eagle-import:TO92-CBE")
      (libsource (lib "eagle-import") (part "-NPN-TO92-CBEMPS2222A"))
    )
    (comp (ref "T43")
      (value "MPS2222A-NPN-TO92-CBE")
      (footprint "eagle-import:TO92-CBE")
      (libsource (lib "eagle-import") (part "-NPN-TO92-CBEMPS2222A"))
    )
    (comp (ref "T44")
      (value "MPS2222A-NPN-TO92-CBE")
      (footprint "eagle-import:TO92-CBE")
      (libsource (lib "eagle-import") (part "-NPN-TO92-CBEMPS2222A"))
    )
    (comp (ref "T45")
      (value "MPS2222A-NPN-TO92-CBE")
      (footprint "eagle-import:TO92-CBE")
      (libsource (lib "eagle-import") (part "-NPN-TO92-CBEMPS2222A"))
    )
    (comp (ref "T46")
      (value "MPS2222A-NPN-TO92-CBE")
      (footprint "eagle-import:TO92-CBE")
      (libsource (lib "eagle-import") (part "-NPN-TO92-CBEMPS2222A"))
    )
    (comp (ref "T47")
      (value "MPS2222A-NPN-TO92-CBE")
      (footprint "eagle-import:TO92-CBE")
      (libsource (lib "eagle-import") (part "-NPN-TO92-CBEMPS2222A"))
    )
    (comp (ref "T48")
      (value "MPS2222A-NPN-TO92-CBE")
      (footprint "eagle-import:TO92-CBE")
      (libsource (lib "eagle-import") (part "-NPN-TO92-CBEMPS2222A"))
    )
    (comp (ref "T49")
      (value "MPS2222A-NPN-TO92-CBE")
      (footprint "eagle-import:TO92-CBE")
      (libsource (lib "eagle-import") (part "-NPN-TO92-CBEMPS2222A"))
    )
    (comp (ref "T50")
      (value "MPS2222A-NPN-TO92-CBE")
      (footprint "eagle-import:TO92-CBE")
      (libsource (lib "eagle-import") (part "-NPN-TO92-CBEMPS2222A"))
    )
    (comp (ref "T51")
      (value "MPS2222A-NPN-TO92-CBE")
      (footprint "eagle-import:TO92-CBE")
      (libsource (lib "eagle-import") (part "-NPN-TO92-CBEMPS2222A"))
    )
    (comp (ref "T52")
      (value "MPS2222A-NPN-TO92-CBE")
      (footprint "eagle-import:TO92-CBE")
      (libsource (lib "eagle-import") (part "-NPN-TO92-CBEMPS2222A"))
    )
    (comp (ref "T53")
      (value "MPS2222A-NPN-TO92-CBE")
      (footprint "eagle-import:TO92-CBE")
      (libsource (lib "eagle-import") (part "-NPN-TO92-CBEMPS2222A"))
    )
    (comp (ref "T54")
      (value "MPS2222A-NPN-TO92-CBE")
      (footprint "eagle-import:TO92-CBE")
      (libsource (lib "eagle-import") (part "-NPN-TO92-CBEMPS2222A"))
    )
    (comp (ref "T55")
      (value "MPS2222A-NPN-TO92-CBE")
      (footprint "eagle-import:TO92-CBE")
      (libsource (lib "eagle-import") (part "-NPN-TO92-CBEMPS2222A"))
    )
    (comp (ref "T56")
      (value "MPS2222A-NPN-TO92-CBE")
      (footprint "eagle-import:TO92-CBE")
      (libsource (lib "eagle-import") (part "-NPN-TO92-CBEMPS2222A"))
    )
    (comp (ref "T57")
      (value "MPS2222A-NPN-TO92-CBE")
      (footprint "eagle-import:TO92-CBE")
      (libsource (lib "eagle-import") (part "-NPN-TO92-CBEMPS2222A"))
    )
    (comp (ref "T58")
      (value "MPS2222A-NPN-TO92-CBE")
      (footprint "eagle-import:TO92-CBE")
      (libsource (lib "eagle-import") (part "-NPN-TO92-CBEMPS2222A"))
    )
    (comp (ref "T59")
      (value "MPS2222A-NPN-TO92-CBE")
      (footprint "eagle-import:TO92-CBE")
      (libsource (lib "eagle-import") (part "-NPN-TO92-CBEMPS2222A"))
    )
    (comp (ref "T60")
      (value "MPS2222A-NPN-TO92-CBE")
      (footprint "eagle-import:TO92-CBE")
      (libsource (lib "eagle-import") (part "-NPN-TO92-CBEMPS2222A"))
    )
    (comp (ref "T61")
      (value "MPS2222A-NPN-TO92-CBE")
      (footprint "eagle-import:TO92-CBE")
      (libsource (lib "eagle-import") (part "-NPN-TO92-CBEMPS2222A"))
    )
    (comp (ref "T62")
      (value "MPS2222A-NPN-TO92-CBE")
      (footprint "eagle-import:TO92-CBE")
      (libsource (lib "eagle-import") (part "-NPN-TO92-CBEMPS2222A"))
    )
    (comp (ref "T63")
      (value "MPS2222A-NPN-TO92-CBE")
      (footprint "eagle-import:TO92-CBE")
      (libsource (lib "eagle-import") (part "-NPN-TO92-CBEMPS2222A"))
    )
    (comp (ref "T64")
      (value "MPS2222A-NPN-TO92-CBE")
      (footprint "eagle-import:TO92-CBE")
      (libsource (lib "eagle-import") (part "-NPN-TO92-CBEMPS2222A"))
    )
    (comp (ref "T65")
      (value "MPS2222A-NPN-TO92-CBE")
      (footprint "eagle-import:TO92-CBE")
      (libsource (lib "eagle-import") (part "-NPN-TO92-CBEMPS2222A"))
    )
    (comp (ref "T66")
      (value "MPS2222A-NPN-TO92-CBE")
      (footprint "eagle-import:TO92-CBE")
      (libsource (lib "eagle-import") (part "-NPN-TO92-CBEMPS2222A"))
    )
    (comp (ref "T67")
      (value "MPS2222A-NPN-TO92-CBE")
      (footprint "eagle-import:TO92-CBE")
      (libsource (lib "eagle-import") (part "-NPN-TO92-CBEMPS2222A"))
    )
    (comp (ref "T68")
      (value "MPS2222A-NPN-TO92-CBE")
      (footprint "eagle-import:TO92-CBE")
      (libsource (lib "eagle-import") (part "-NPN-TO92-CBEMPS2222A"))
    )
    (comp (ref "T69")
      (value "MPS2222A-NPN-TO92-CBE")
      (footprint "eagle-import:TO92-CBE")
      (libsource (lib "eagle-import") (part "-NPN-TO92-CBEMPS2222A"))
    )
    (comp (ref "T70")
      (value "MPS2222A-NPN-TO92-CBE")
      (footprint "eagle-import:TO92-CBE")
      (libsource (lib "eagle-import") (part "-NPN-TO92-CBEMPS2222A"))
    )
    (comp (ref "T71")
      (value "MPS2222A-NPN-TO92-CBE")
      (footprint "eagle-import:TO92-CBE")
      (libsource (lib "eagle-import") (part "-NPN-TO92-CBEMPS2222A"))
    )
    (comp (ref "T72")
      (value "MPS2222A-NPN-TO92-CBE")
      (footprint "eagle-import:TO92-CBE")
      (libsource (lib "eagle-import") (part "-NPN-TO92-CBEMPS2222A"))
    )
    (comp (ref "T73")
      (value "MPS2222A-NPN-TO92-CBE")
      (footprint "eagle-import:TO92-CBE")
      (libsource (lib "eagle-import") (part "-NPN-TO92-CBEMPS2222A"))
    )
    (comp (ref "T74")
      (value "MPS2222A-NPN-TO92-CBE")
      (footprint "eagle-import:TO92-CBE")
      (libsource (lib "eagle-import") (part "-NPN-TO92-CBEMPS2222A"))
    )
    (comp (ref "T75")
      (value "MPS2222A-NPN-TO92-CBE")
      (footprint "eagle-import:TO92-CBE")
      (libsource (lib "eagle-import") (part "-NPN-TO92-CBEMPS2222A"))
    )
    (comp (ref "T76")
      (value "MPS2222A-NPN-TO92-CBE")
      (footprint "eagle-import:TO92-CBE")
      (libsource (lib "eagle-import") (part "-NPN-TO92-CBEMPS2222A"))
    )
    (comp (ref "T77")
      (value "MPS2222A-NPN-TO92-CBE")
      (footprint "eagle-import:TO92-CBE")
      (libsource (lib "eagle-import") (part "-NPN-TO92-CBEMPS2222A"))
    )
    (comp (ref "T78")
      (value "MPS2222A-NPN-TO92-CBE")
      (footprint "eagle-import:TO92-CBE")
      (libsource (lib "eagle-import") (part "-NPN-TO92-CBEMPS2222A"))
    )
    (comp (ref "T79")
      (value "MPS2222A-NPN-TO92-CBE")
      (footprint "eagle-import:TO92-CBE")
      (libsource (lib "eagle-import") (part "-NPN-TO92-CBEMPS2222A"))
    )
    (comp (ref "T80")
      (value "MPS2222A-NPN-TO92-CBE")
      (footprint "eagle-import:TO92-CBE")
      (libsource (lib "eagle-import") (part "-NPN-TO92-CBEMPS2222A"))
    )
    (comp (ref "T81")
      (value "MPS2222A-NPN-TO92-CBE")
      (footprint "eagle-import:TO92-CBE")
      (libsource (lib "eagle-import") (part "-NPN-TO92-CBEMPS2222A"))
    )
    (comp (ref "T82")
      (value "MPS2222A-NPN-TO92-CBE")
      (footprint "eagle-import:TO92-CBE")
      (libsource (lib "eagle-import") (part "-NPN-TO92-CBEMPS2222A"))
    )
    (comp (ref "T83")
      (value "MPS2222A-NPN-TO92-CBE")
      (footprint "eagle-import:TO92-CBE")
      (libsource (lib "eagle-import") (part "-NPN-TO92-CBEMPS2222A"))
    )
    (comp (ref "T84")
      (value "MPS2222A-NPN-TO92-CBE")
      (footprint "eagle-import:TO92-CBE")
      (libsource (lib "eagle-import") (part "-NPN-TO92-CBEMPS2222A"))
    )
    (comp (ref "T85")
      (value "MPS2222A-NPN-TO92-CBE")
      (footprint "eagle-import:TO92-CBE")
      (libsource (lib "eagle-import") (part "-NPN-TO92-CBEMPS2222A"))
    )
    (comp (ref "T86")
      (value "MPS2222A-NPN-TO92-CBE")
      (footprint "eagle-import:TO92-CBE")
      (libsource (lib "eagle-import") (part "-NPN-TO92-CBEMPS2222A"))
    )
    (comp (ref "T87")
      (value "MPS2222A-NPN-TO92-CBE")
      (footprint "eagle-import:TO92-CBE")
      (libsource (lib "eagle-import") (part "-NPN-TO92-CBEMPS2222A"))
    )
    (comp (ref "T88")
      (value "MPS2222A-NPN-TO92-CBE")
      (footprint "eagle-import:TO92-CBE")
      (libsource (lib "eagle-import") (part "-NPN-TO92-CBEMPS2222A"))
    )
    (comp (ref "T89")
      (value "MPS2222A-NPN-TO92-CBE")
      (footprint "eagle-import:TO92-CBE")
      (libsource (lib "eagle-import") (part "-NPN-TO92-CBEMPS2222A"))
    )
    (comp (ref "TAD")
      (value "BULB")
      (footprint "eagle-import:BULB")
      (libsource (lib "eagle-import") (part "BULB"))
    )
    (comp (ref "WORDCOUNT")
      (value "BULB")
      (footprint "eagle-import:BULB")
      (libsource (lib "eagle-import") (part "BULB"))
    )
    (comp (ref "C40")
      (value "MA17-2")
      (footprint "eagle-import:MA17-2")
      (libsource (lib "eagle-import") (part "MA17-2"))
    )
    (comp (ref "D40")
      (value "MA17-2")
      (footprint "eagle-import:MA17-2")
      (libsource (lib "eagle-import") (part "MA17-2"))
    )
    (comp (ref "E40")
      (value "MA17-2")
      (footprint "eagle-import:MA17-2")
      (libsource (lib "eagle-import") (part "MA17-2"))
    )
    (comp (ref "F40")
      (value "MA17-2")
      (footprint "eagle-import:MA17-2")
      (libsource (lib "eagle-import") (part "MA17-2"))
    )
    (comp (ref "U$10")
      (value "QUAD")
      (footprint "eagle-import:EDGE-CON8")
      (libsource (lib "eagle-import") (part "QUAD"))
    )
  )
  (nets
    (net (code "1") (name "+15V") (class "Default")
      (node (ref "+V1") (pin "1") (pinfunction "1_1") (pintype "passive"))
      (node (ref "+V2") (pin "1") (pinfunction "1_1") (pintype "passive"))
      (node (ref "+V3") (pin "1") (pinfunction "1_1") (pintype "passive"))
      (node (ref "+V4") (pin "1") (pinfunction "1_1") (pintype "passive"))
      (node (ref "R1") (pin "1") (pinfunction "1_1") (pintype "passive"))
      (node (ref "R10") (pin "1") (pinfunction "1_1") (pintype "passive"))
      (node (ref "R11") (pin "1") (pinfunction "1_1") (pintype "passive"))
      (node (ref "R12") (pin "1") (pinfunction "1_1") (pintype "passive"))
      (node (ref "R13") (pin "1") (pinfunction "1_1") (pintype "passive"))
      (node (ref "R14") (pin "1") (pinfunction "1_1") (pintype "passive"))
      (node (ref "R15") (pin "1") (pinfunction "1_1") (pintype "passive"))
      (node (ref "R16") (pin "1") (pinfunction "1_1") (pintype "passive"))
      (node (ref "R17") (pin "1") (pinfunction "1_1") (pintype "passive"))
      (node (ref "R18") (pin "1") (pinfunction "1_1") (pintype "passive"))
      (node (ref "R19") (pin "1") (pinfunction "1_1") (pintype "passive"))
      (node (ref "R2") (pin "1") (pinfunction "1_1") (pintype "passive"))
      (node (ref "R20") (pin "1") (pinfunction "1_1") (pintype "passive"))
      (node (ref "R21") (pin "1") (pinfunction "1_1") (pintype "passive"))
      (node (ref "R22") (pin "1") (pinfunction "1_1") (pintype "passive"))
      (node (ref "R23") (pin "1") (pinfunction "1_1") (pintype "passive"))
      (node (ref "R24") (pin "1") (pinfunction "1_1") (pintype "passive"))
      (node (ref "R25") (pin "1") (pinfunction "1_1") (pintype "passive"))
      (node (ref "R26") (pin "1") (pinfunction "1_1") (pintype "passive"))
      (node (ref "R27") (pin "1") (pinfunction "1_1") (pintype "passive"))
      (node (ref "R28") (pin "1") (pinfunction "1_1") (pintype "passive"))
      (node (ref "R29") (pin "1") (pinfunction "1_1") (pintype "passive"))
      (node (ref "R3") (pin "1") (pinfunction "1_1") (pintype "passive"))
      (node (ref "R30") (pin "1") (pinfunction "1_1") (pintype "passive"))
      (node (ref "R31") (pin "1") (pinfunction "1_1") (pintype "passive"))
      (node (ref "R32") (pin "1") (pinfunction "1_1") (pintype "passive"))
      (node (ref "R33") (pin "1") (pinfunction "1_1") (pintype "passive"))
      (node (ref "R34") (pin "1") (pinfunction "1_1") (pintype "passive"))
      (node (ref "R35") (pin "1") (pinfunction "1_1") (pintype "passive"))
      (node (ref "R36") (pin "1") (pinfunction "1_1") (pintype "passive"))
      (node (ref "R37") (pin "1") (pinfunction "1_1") (pintype "passive"))
      (node (ref "R38") (pin "1") (pinfunction "1_1") (pintype "passive"))
      (node (ref "R39") (pin "1") (pinfunction "1_1") (pintype "passive"))
      (node (ref "R4") (pin "1") (pinfunction "1_1") (pintype "passive"))
      (node (ref "R40") (pin "1") (pinfunction "1_1") (pintype "passive"))
      (node (ref "R41") (pin "1") (pinfunction "1_1") (pintype "passive"))
      (node (ref "R42") (pin "1") (pinfunction "1_1") (pintype "passive"))
      (node (ref "R43") (pin "1") (pinfunction "1_1") (pintype "passive"))
      (node (ref "R44") (pin "1") (pinfunction "1_1") (pintype "passive"))
      (node (ref "R45") (pin "1") (pinfunction "1_1") (pintype "passive"))
      (node (ref "R46") (pin "1") (pinfunction "1_1") (pintype "passive"))
      (node (ref "R47") (pin "1") (pinfunction "1_1") (pintype "passive"))
      (node (ref "R48") (pin "1") (pinfunction "1_1") (pintype "passive"))
      (node (ref "R49") (pin "1") (pinfunction "1_1") (pintype "passive"))
      (node (ref "R5") (pin "1") (pinfunction "1_1") (pintype "passive"))
      (node (ref "R50") (pin "1") (pinfunction "1_1") (pintype "passive"))
      (node (ref "R51") (pin "1") (pinfunction "1_1") (pintype "passive"))
      (node (ref "R52") (pin "1") (pinfunction "1_1") (pintype "passive"))
      (node (ref "R53") (pin "1") (pinfunction "1_1") (pintype "passive"))
      (node (ref "R54") (pin "1") (pinfunction "1_1") (pintype "passive"))
      (node (ref "R55") (pin "1") (pinfunction "1_1") (pintype "passive"))
      (node (ref "R56") (pin "1") (pinfunction "1_1") (pintype "passive"))
      (node (ref "R57") (pin "1") (pinfunction "1_1") (pintype "passive"))
      (node (ref "R58") (pin "1") (pinfunction "1_1") (pintype "passive"))
      (node (ref "R59") (pin "1") (pinfunction "1_1") (pintype "passive"))
      (node (ref "R6") (pin "1") (pinfunction "1_1") (pintype "passive"))
      (node (ref "R60") (pin "1") (pinfunction "1_1") (pintype "passive"))
      (node (ref "R61") (pin "1") (pinfunction "1_1") (pintype "passive"))
      (node (ref "R62") (pin "1") (pinfunction "1_1") (pintype "passive"))
      (node (ref "R63") (pin "1") (pinfunction "1_1") (pintype "passive"))
      (node (ref "R64") (pin "1") (pinfunction "1_1") (pintype "passive"))
      (node (ref "R65") (pin "1") (pinfunction "1_1") (pintype "passive"))
      (node (ref "R66") (pin "1") (pinfunction "1_1") (pintype "passive"))
      (node (ref "R67") (pin "1") (pinfunction "1_1") (pintype "passive"))
      (node (ref "R68") (pin "1") (pinfunction "1_1") (pintype "passive"))
      (node (ref "R69") (pin "1") (pinfunction "1_1") (pintype "passive"))
      (node (ref "R7") (pin "1") (pinfunction "1_1") (pintype "passive"))
      (node (ref "R70") (pin "1") (pinfunction "1_1") (pintype "passive"))
      (node (ref "R71") (pin "1") (pinfunction "1_1") (pintype "passive"))
      (node (ref "R72") (pin "1") (pinfunction "1_1") (pintype "passive"))
      (node (ref "R73") (pin "1") (pinfunction "1_1") (pintype "passive"))
      (node (ref "R74") (pin "1") (pinfunction "1_1") (pintype "passive"))
      (node (ref "R75") (pin "1") (pinfunction "1_1") (pintype "passive"))
      (node (ref "R76") (pin "1") (pinfunction "1_1") (pintype "passive"))
      (node (ref "R77") (pin "1") (pinfunction "1_1") (pintype "passive"))
      (node (ref "R78") (pin "1") (pinfunction "1_1") (pintype "passive"))
      (node (ref "R79") (pin "1") (pinfunction "1_1") (pintype "passive"))
      (node (ref "R8") (pin "1") (pinfunction "1_1") (pintype "passive"))
      (node (ref "R80") (pin "1") (pinfunction "1_1") (pintype "passive"))
      (node (ref "R81") (pin "1") (pinfunction "1_1") (pintype "passive"))
      (node (ref "R82") (pin "1") (pinfunction "1_1") (pintype "passive"))
      (node (ref "R83") (pin "1") (pinfunction "1_1") (pintype "passive"))
      (node (ref "R84") (pin "1") (pinfunction "1_1") (pintype "passive"))
      (node (ref "R85") (pin "1") (pinfunction "1_1") (pintype "passive"))
      (node (ref "R86") (pin "1") (pinfunction "1_1") (pintype "passive"))
      (node (ref "R87") (pin "1") (pinfunction "1_1") (pintype "passive"))
      (node (ref "R88") (pin "1") (pinfunction "1_1") (pintype "passive"))
      (node (ref "R89") (pin "1") (pinfunction "1_1") (pintype "passive"))
      (node (ref "R9") (pin "1") (pinfunction "1_1") (pintype "passive"))
    )
    (net (code "2") (name "AC0") (class "Default")
      (node (ref "D40TOP") (pin "4") (pinfunction "1_4") (pintype "passive"))
      (node (ref "E40") (pin "7") (pinfunction "7_7") (pintype "passive"))
      (node (ref "T43") (pin "B") (pinfunction "B_B") (pintype "passive"))
    )
    (net (code "3") (name "AC1") (class "Default")
      (node (ref "D40BOT") (pin "2") (pinfunction "1_2") (pintype "passive"))
      (node (ref "E40") (pin "4") (pinfunction "4_4") (pintype "passive"))
      (node (ref "T44") (pin "B") (pinfunction "B_B") (pintype "passive"))
    )
    (net (code "4") (name "AC2") (class "Default")
      (node (ref "D40TOP") (pin "12") (pinfunction "1_12") (pintype "passive"))
      (node (ref "E40") (pin "21") (pinfunction "21_21") (pintype "passive"))
      (node (ref "T45") (pin "B") (pinfunction "B_B") (pintype "passive"))
    )
    (net (code "5") (name "AC3") (class "Default")
      (node (ref "D40BOT") (pin "9") (pinfunction "1_9") (pintype "passive"))
      (node (ref "E40") (pin "14") (pinfunction "14_14") (pintype "passive"))
      (node (ref "T46") (pin "B") (pinfunction "B_B") (pintype "passive"))
    )
    (net (code "6") (name "AC4") (class "Default")
      (node (ref "D40TOP") (pin "17") (pinfunction "1_17") (pintype "passive"))
      (node (ref "E40") (pin "31") (pinfunction "31_31") (pintype "passive"))
      (node (ref "T47") (pin "B") (pinfunction "B_B") (pintype "passive"))
    )
    (net (code "7") (name "AC5") (class "Default")
      (node (ref "D40BOT") (pin "16") (pinfunction "1_16") (pintype "passive"))
      (node (ref "E40") (pin "28") (pinfunction "28_28") (pintype "passive"))
      (node (ref "T48") (pin "B") (pinfunction "B_B") (pintype "passive"))
    )
    (net (code "8") (name "AC6") (class "Default")
      (node (ref "E40TOP") (pin "4") (pinfunction "1_4") (pintype "passive"))
      (node (ref "F40") (pin "7") (pinfunction "7_7") (pintype "passive"))
      (node (ref "T49") (pin "B") (pinfunction "B_B") (pintype "passive"))
    )
    (net (code "9") (name "AC7") (class "Default")
      (node (ref "E40BOT") (pin "2") (pinfunction "1_2") (pintype "passive"))
      (node (ref "F40") (pin "4") (pinfunction "4_4") (pintype "passive"))
      (node (ref "T50") (pin "B") (pinfunction "B_B") (pintype "passive"))
    )
    (net (code "10") (name "AC8") (class "Default")
      (node (ref "E40TOP") (pin "12") (pinfunction "1_12") (pintype "passive"))
      (node (ref "F40") (pin "21") (pinfunction "21_21") (pintype "passive"))
      (node (ref "T51") (pin "B") (pinfunction "B_B") (pintype "passive"))
    )
    (net (code "11") (name "AC9") (class "Default")
      (node (ref "E40BOT") (pin "9") (pinfunction "1_9") (pintype "passive"))
      (node (ref "F40") (pin "14") (pinfunction "14_14") (pintype "passive"))
      (node (ref "T52") (pin "B") (pinfunction "B_B") (pintype "passive"))
    )
    (net (code "12") (name "AC10") (class "Default")
      (node (ref "E40TOP") (pin "17") (pinfunction "1_17") (pintype "passive"))
      (node (ref "F40") (pin "31") (pinfunction "31_31") (pintype "passive"))
      (node (ref "T53") (pin "B") (pinfunction "B_B") (pintype "passive"))
    )
    (net (code "13") (name "AC11") (class "Default")
      (node (ref "E40BOT") (pin "16") (pinfunction "1_16") (pintype "passive"))
      (node (ref "F40") (pin "28") (pinfunction "28_28") (pintype "passive"))
      (node (ref "T54") (pin "B") (pinfunction "B_B") (pintype "passive"))
    )
    (net (code "14") (name "AND") (class "Default")
      (node (ref "D40") (pin "2") (pinfunction "2_2") (pintype "passive"))
      (node (ref "F40BOT") (pin "1") (pinfunction "1_1") (pintype "passive"))
      (node (ref "T82") (pin "B") (pinfunction "B_B") (pintype "passive"))
    )
    (net (code "15") (name "BREAK") (class "Default")
      (node (ref "D40") (pin "22") (pinfunction "22_22") (pintype "passive"))
      (node (ref "F40BOT") (pin "12") (pinfunction "1_12") (pintype "passive"))
      (node (ref "T81") (pin "B") (pinfunction "B_B") (pintype "passive"))
    )
    (net (code "16") (name "CA") (class "Default")
      (node (ref "D40") (pin "32") (pinfunction "32_32") (pintype "passive"))
      (node (ref "F40BOT") (pin "18") (pinfunction "1_18") (pintype "passive"))
      (node (ref "T80") (pin "B") (pinfunction "B_B") (pintype "passive"))
    )
    (net (code "17") (name "DCA") (class "Default")
      (node (ref "D40") (pin "8") (pinfunction "8_8") (pintype "passive"))
      (node (ref "F40BOT") (pin "4") (pinfunction "1_4") (pintype "passive"))
      (node (ref "T85") (pin "B") (pinfunction "B_B") (pintype "passive"))
    )
    (net (code "18") (name "DEFER") (class "Default")
      (node (ref "D40") (pin "26") (pinfunction "26_26") (pintype "passive"))
      (node (ref "F40BOT") (pin "15") (pinfunction "1_15") (pintype "passive"))
      (node (ref "T78") (pin "B") (pinfunction "B_B") (pintype "passive"))
    )
    (net (code "19") (name "DF0") (class "Default")
      (node (ref "C40") (pin "1") (pinfunction "1_1") (pintype "passive"))
      (node (ref "C40TOP") (pin "1") (pinfunction "1_1") (pintype "passive"))
      (node (ref "T1") (pin "B") (pinfunction "B_B") (pintype "passive"))
    )
    (net (code "20") (name "DF1") (class "Default")
      (node (ref "C40") (pin "10") (pinfunction "10_10") (pintype "passive"))
      (node (ref "C40BOT") (pin "5") (pinfunction "1_5") (pintype "passive"))
      (node (ref "T2") (pin "B") (pinfunction "B_B") (pintype "passive"))
    )
    (net (code "21") (name "DF2") (class "Default")
      (node (ref "C40") (pin "11") (pinfunction "11_11") (pintype "passive"))
      (node (ref "C40TOP") (pin "6") (pinfunction "1_6") (pintype "passive"))
      (node (ref "T3") (pin "B") (pinfunction "B_B") (pintype "passive"))
    )
    (net (code "22") (name "EXECUTE") (class "Default")
      (node (ref "D40") (pin "28") (pinfunction "28_28") (pintype "passive"))
      (node (ref "F40BOT") (pin "16") (pinfunction "1_16") (pintype "passive"))
      (node (ref "T77") (pin "B") (pinfunction "B_B") (pintype "passive"))
    )
    (net (code "23") (name "FETCH") (class "Default")
      (node (ref "D40") (pin "24") (pinfunction "24_24") (pintype "passive"))
      (node (ref "F40BOT") (pin "14") (pinfunction "1_14") (pintype "passive"))
      (node (ref "T76") (pin "B") (pinfunction "B_B") (pintype "passive"))
    )
    (net (code "24") (name "GND") (class "Default")
      (node (ref "C40") (pin "17") (pinfunction "17_17") (pintype "passive"))
      (node (ref "C40") (pin "18") (pinfunction "18_18") (pintype "passive"))
      (node (ref "C40") (pin "19") (pinfunction "19_19") (pintype "passive"))
      (node (ref "C40") (pin "20") (pinfunction "20_20") (pintype "passive"))
      (node (ref "C40BOT") (pin "13") (pinfunction "1_13") (pintype "passive"))
      (node (ref "D40") (pin "17") (pinfunction "17_17") (pintype "passive"))
      (node (ref "D40") (pin "18") (pinfunction "18_18") (pintype "passive"))
      (node (ref "D40") (pin "19") (pinfunction "19_19") (pintype "passive"))
      (node (ref "D40") (pin "20") (pinfunction "20_20") (pintype "passive"))
      (node (ref "D40BOT") (pin "13") (pinfunction "1_13") (pintype "passive"))
      (node (ref "E40") (pin "17") (pinfunction "17_17") (pintype "passive"))
      (node (ref "E40") (pin "18") (pinfunction "18_18") (pintype "passive"))
      (node (ref "E40") (pin "19") (pinfunction "19_19") (pintype "passive"))
      (node (ref "E40") (pin "20") (pinfunction "20_20") (pintype "passive"))
      (node (ref "E40BOT") (pin "13") (pinfunction "1_13") (pintype "passive"))
      (node (ref "F40") (pin "17") (pinfunction "17_17") (pintype "passive"))
      (node (ref "F40") (pin "18") (pinfunction "18_18") (pintype "passive"))
      (node (ref "F40") (pin "19") (pinfunction "19_19") (pintype "passive"))
      (node (ref "F40") (pin "20") (pinfunction "20_20") (pintype "passive"))
      (node (ref "F40BOT") (pin "13") (pinfunction "1_13") (pintype "passive"))
      (node (ref "GND1") (pin "1") (pinfunction "1_1") (pintype "passive"))
      (node (ref "GND2") (pin "1") (pinfunction "1_1") (pintype "passive"))
      (node (ref "GND3") (pin "1") (pinfunction "1_1") (pintype "passive"))
      (node (ref "GND4") (pin "1") (pinfunction "1_1") (pintype "passive"))
      (node (ref "T1") (pin "E") (pinfunction "E_E") (pintype "passive"))
      (node (ref "T10") (pin "E") (pinfunction "E_E") (pintype "passive"))
      (node (ref "T11") (pin "E") (pinfunction "E_E") (pintype "passive"))
      (node (ref "T12") (pin "E") (pinfunction "E_E") (pintype "passive"))
      (node (ref "T13") (pin "E") (pinfunction "E_E") (pintype "passive"))
      (node (ref "T14") (pin "E") (pinfunction "E_E") (pintype "passive"))
      (node (ref "T15") (pin "E") (pinfunction "E_E") (pintype "passive"))
      (node (ref "T16") (pin "E") (pinfunction "E_E") (pintype "passive"))
      (node (ref "T17") (pin "E") (pinfunction "E_E") (pintype "passive"))
      (node (ref "T18") (pin "E") (pinfunction "E_E") (pintype "passive"))
      (node (ref "T19") (pin "E") (pinfunction "E_E") (pintype "passive"))
      (node (ref "T2") (pin "E") (pinfunction "E_E") (pintype "passive"))
      (node (ref "T20") (pin "E") (pinfunction "E_E") (pintype "passive"))
      (node (ref "T21") (pin "E") (pinfunction "E_E") (pintype "passive"))
      (node (ref "T22") (pin "E") (pinfunction "E_E") (pintype "passive"))
      (node (ref "T23") (pin "E") (pinfunction "E_E") (pintype "passive"))
      (node (ref "T24") (pin "E") (pinfunction "E_E") (pintype "passive"))
      (node (ref "T25") (pin "E") (pinfunction "E_E") (pintype "passive"))
      (node (ref "T26") (pin "E") (pinfunction "E_E") (pintype "passive"))
      (node (ref "T27") (pin "E") (pinfunction "E_E") (pintype "passive"))
      (node (ref "T28") (pin "E") (pinfunction "E_E") (pintype "passive"))
      (node (ref "T29") (pin "E") (pinfunction "E_E") (pintype "passive"))
      (node (ref "T3") (pin "E") (pinfunction "E_E") (pintype "passive"))
      (node (ref "T30") (pin "E") (pinfunction "E_E") (pintype "passive"))
      (node (ref "T31") (pin "E") (pinfunction "E_E") (pintype "passive"))
      (node (ref "T32") (pin "E") (pinfunction "E_E") (pintype "passive"))
      (node (ref "T33") (pin "E") (pinfunction "E_E") (pintype "passive"))
      (node (ref "T34") (pin "E") (pinfunction "E_E") (pintype "passive"))
      (node (ref "T35") (pin "E") (pinfunction "E_E") (pintype "passive"))
      (node (ref "T36") (pin "E") (pinfunction "E_E") (pintype "passive"))
      (node (ref "T37") (pin "E") (pinfunction "E_E") (pintype "passive"))
      (node (ref "T38") (pin "E") (pinfunction "E_E") (pintype "passive"))
      (node (ref "T39") (pin "E") (pinfunction "E_E") (pintype "passive"))
      (node (ref "T4") (pin "E") (pinfunction "E_E") (pintype "passive"))
      (node (ref "T40") (pin "E") (pinfunction "E_E") (pintype "passive"))
      (node (ref "T41") (pin "E") (pinfunction "E_E") (pintype "passive"))
      (node (ref "T42") (pin "E") (pinfunction "E_E") (pintype "passive"))
      (node (ref "T43") (pin "E") (pinfunction "E_E") (pintype "passive"))
      (node (ref "T44") (pin "E") (pinfunction "E_E") (pintype "passive"))
      (node (ref "T45") (pin "E") (pinfunction "E_E") (pintype "passive"))
      (node (ref "T46") (pin "E") (pinfunction "E_E") (pintype "passive"))
      (node (ref "T47") (pin "E") (pinfunction "E_E") (pintype "passive"))
      (node (ref "T48") (pin "E") (pinfunction "E_E") (pintype "passive"))
      (node (ref "T49") (pin "E") (pinfunction "E_E") (pintype "passive"))
      (node (ref "T5") (pin "E") (pinfunction "E_E") (pintype "passive"))
      (node (ref "T50") (pin "E") (pinfunction "E_E") (pintype "passive"))
      (node (ref "T51") (pin "E") (pinfunction "E_E") (pintype "passive"))
      (node (ref "T52") (pin "E") (pinfunction "E_E") (pintype "passive"))
      (node (ref "T53") (pin "E") (pinfunction "E_E") (pintype "passive"))
      (node (ref "T54") (pin "E") (pinfunction "E_E") (pintype "passive"))
      (node (ref "T55") (pin "E") (pinfunction "E_E") (pintype "passive"))
      (node (ref "T56") (pin "E") (pinfunction "E_E") (pintype "passive"))
      (node (ref "T57") (pin "E") (pinfunction "E_E") (pintype "passive"))
      (node (ref "T58") (pin "E") (pinfunction "E_E") (pintype "passive"))
      (node (ref "T59") (pin "E") (pinfunction "E_E") (pintype "passive"))
      (node (ref "T6") (pin "E") (pinfunction "E_E") (pintype "passive"))
      (node (ref "T60") (pin "E") (pinfunction "E_E") (pintype "passive"))
      (node (ref "T61") (pin "E") (pinfunction "E_E") (pintype "passive"))
      (node (ref "T62") (pin "E") (pinfunction "E_E") (pintype "passive"))
      (node (ref "T63") (pin "E") (pinfunction "E_E") (pintype "passive"))
      (node (ref "T64") (pin "E") (pinfunction "E_E") (pintype "passive"))
      (node (ref "T65") (pin "E") (pinfunction "E_E") (pintype "passive"))
      (node (ref "T66") (pin "E") (pinfunction "E_E") (pintype "passive"))
      (node (ref "T67") (pin "E") (pinfunction "E_E") (pintype "passive"))
      (node (ref "T68") (pin "E") (pinfunction "E_E") (pintype "passive"))
      (node (ref "T69") (pin "E") (pinfunction "E_E") (pintype "passive"))
      (node (ref "T7") (pin "E") (pinfunction "E_E") (pintype "passive"))
      (node (ref "T70") (pin "E") (pinfunction "E_E") (pintype "passive"))
      (node (ref "T71") (pin "E") (pinfunction "E_E") (pintype "passive"))
      (node (ref "T72") (pin "E") (pinfunction "E_E") (pintype "passive"))
      (node (ref "T73") (pin "E") (pinfunction "E_E") (pintype "passive"))
      (node (ref "T74") (pin "E") (pinfunction "E_E") (pintype "passive"))
      (node (ref "T75") (pin "E") (pinfunction "E_E") (pintype "passive"))
      (node (ref "T76") (pin "E") (pinfunction "E_E") (pintype "passive"))
      (node (ref "T77") (pin "E") (pinfunction "E_E") (pintype "passive"))
      (node (ref "T78") (pin "E") (pinfunction "E_E") (pintype "passive"))
      (node (ref "T79") (pin "E") (pinfunction "E_E") (pintype "passive"))
      (node (ref "T8") (pin "E") (pinfunction "E_E") (pintype "passive"))
      (node (ref "T80") (pin "E") (pinfunction "E_E") (pintype "passive"))
      (node (ref "T81") (pin "E") (pinfunction "E_E") (pintype "passive"))
      (node (ref "T82") (pin "E") (pinfunction "E_E") (pintype "passive"))
      (node (ref "T83") (pin "E") (pinfunction "E_E") (pintype "passive"))
      (node (ref "T84") (pin "E") (pinfunction "E_E") (pintype "passive"))
      (node (ref "T85") (pin "E") (pinfunction "E_E") (pintype "passive"))
      (node (ref "T86") (pin "E") (pinfunction "E_E") (pintype "passive"))
      (node (ref "T87") (pin "E") (pinfunction "E_E") (pintype "passive"))
      (node (ref "T88") (pin "E") (pinfunction "E_E") (pintype "passive"))
      (node (ref "T89") (pin "E") (pinfunction "E_E") (pintype "passive"))
      (node (ref "T9") (pin "E") (pinfunction "E_E") (pintype "passive"))
    )
    (net (code "25") (name "IF0") (class "Default")
      (node (ref "C40") (pin "24") (pinfunction "24_24") (pintype "passive"))
      (node (ref "C40BOT") (pin "14") (pinfunction "1_14") (pintype "passive"))
      (node (ref "T4") (pin "B") (pinfunction "B_B") (pintype "passive"))
    )
    (net (code "26") (name "IF1") (class "Default")
      (node (ref "C40") (pin "25") (pinfunction "25_25") (pintype "passive"))
      (node (ref "C40TOP") (pin "14") (pinfunction "1_14") (pintype "passive"))
      (node (ref "T5") (pin "B") (pinfunction "B_B") (pintype "passive"))
    )
    (net (code "27") (name "IF2") (class "Default")
      (node (ref "C40") (pin "34") (pinfunction "34_34") (pintype "passive"))
      (node (ref "C40BOT") (pin "19") (pinfunction "1_19") (pintype "passive"))
      (node (ref "T6") (pin "B") (pinfunction "B_B") (pintype "passive"))
    )
    (net (code "28") (name "ION") (class "Default")
      (node (ref "D40") (pin "34") (pinfunction "34_34") (pintype "passive"))
      (node (ref "F40BOT") (pin "19") (pinfunction "1_19") (pintype "passive"))
      (node (ref "T73") (pin "B") (pinfunction "B_B") (pintype "passive"))
    )
    (net (code "29") (name "IOT") (class "Default")
      (node (ref "D40") (pin "23") (pinfunction "23_23") (pintype "passive"))
      (node (ref "F40TOP") (pin "13") (pinfunction "1_13") (pintype "passive"))
      (node (ref "T88") (pin "B") (pinfunction "B_B") (pintype "passive"))
    )
    (net (code "30") (name "ISZ") (class "Default")
      (node (ref "D40") (pin "6") (pinfunction "6_6") (pintype "passive"))
      (node (ref "F40BOT") (pin "3") (pinfunction "1_3") (pintype "passive"))
      (node (ref "T84") (pin "B") (pinfunction "B_B") (pintype "passive"))
    )
    (net (code "31") (name "JMP") (class "Default")
      (node (ref "D40") (pin "12") (pinfunction "12_12") (pintype "passive"))
      (node (ref "F40BOT") (pin "6") (pinfunction "1_6") (pintype "passive"))
      (node (ref "T87") (pin "B") (pinfunction "B_B") (pintype "passive"))
    )
    (net (code "32") (name "JMS") (class "Default")
      (node (ref "D40") (pin "10") (pinfunction "10_10") (pintype "passive"))
      (node (ref "F40BOT") (pin "5") (pinfunction "1_5") (pintype "passive"))
      (node (ref "T86") (pin "B") (pinfunction "B_B") (pintype "passive"))
    )
    (net (code "33") (name "LINK") (class "Default")
      (node (ref "C40") (pin "28") (pinfunction "28_28") (pintype "passive"))
      (node (ref "C40BOT") (pin "16") (pinfunction "1_16") (pintype "passive"))
      (node (ref "T72") (pin "B") (pinfunction "B_B") (pintype "passive"))
    )
    (net (code "34") (name "MA0") (class "Default")
      (node (ref "D40TOP") (pin "2") (pinfunction "1_2") (pintype "passive"))
      (node (ref "E40") (pin "3") (pinfunction "3_3") (pintype "passive"))
      (node (ref "T19") (pin "B") (pinfunction "B_B") (pintype "passive"))
    )
    (net (code "35") (name "MA1") (class "Default")
      (node (ref "D40BOT") (pin "4") (pinfunction "1_4") (pintype "passive"))
      (node (ref "E40") (pin "8") (pinfunction "8_8") (pintype "passive"))
      (node (ref "T20") (pin "B") (pinfunction "B_B") (pintype "passive"))
    )
    (net (code "36") (name "MA2") (class "Default")
      (node (ref "D40TOP") (pin "7") (pinfunction "1_7") (pintype "passive"))
      (node (ref "E40") (pin "13") (pinfunction "13_13") (pintype "passive"))
      (node (ref "T21") (pin "B") (pinfunction "B_B") (pintype "passive"))
    )
    (net (code "37") (name "MA3") (class "Default")
      (node (ref "D40BOT") (pin "12") (pinfunction "1_12") (pintype "passive"))
      (node (ref "E40") (pin "22") (pinfunction "22_22") (pintype "passive"))
      (node (ref "T22") (pin "B") (pinfunction "B_B") (pintype "passive"))
    )
    (net (code "38") (name "MA4") (class "Default")
      (node (ref "D40TOP") (pin "15") (pinfunction "1_15") (pintype "passive"))
      (node (ref "E40") (pin "27") (pinfunction "27_27") (pintype "passive"))
      (node (ref "T23") (pin "B") (pinfunction "B_B") (pintype "passive"))
    )
    (net (code "39") (name "MA5") (class "Default")
      (node (ref "D40BOT") (pin "18") (pinfunction "1_18") (pintype "passive"))
      (node (ref "E40") (pin "32") (pinfunction "32_32") (pintype "passive"))
      (node (ref "T24") (pin "B") (pinfunction "B_B") (pintype "passive"))
    )
    (net (code "40") (name "MA6") (class "Default")
      (node (ref "E40TOP") (pin "2") (pinfunction "1_2") (pintype "passive"))
      (node (ref "F40") (pin "3") (pinfunction "3_3") (pintype "passive"))
      (node (ref "T25") (pin "B") (pinfunction "B_B") (pintype "passive"))
    )
    (net (code "41") (name "MA7") (class "Default")
      (node (ref "E40BOT") (pin "4") (pinfunction "1_4") (pintype "passive"))
      (node (ref "F40") (pin "8") (pinfunction "8_8") (pintype "passive"))
      (node (ref "T26") (pin "B") (pinfunction "B_B") (pintype "passive"))
    )
    (net (code "42") (name "MA8") (class "Default")
      (node (ref "E40TOP") (pin "7") (pinfunction "1_7") (pintype "passive"))
      (node (ref "F40") (pin "13") (pinfunction "13_13") (pintype "passive"))
      (node (ref "T27") (pin "B") (pinfunction "B_B") (pintype "passive"))
    )
    (net (code "43") (name "MA9") (class "Default")
      (node (ref "E40BOT") (pin "12") (pinfunction "1_12") (pintype "passive"))
      (node (ref "F40") (pin "22") (pinfunction "22_22") (pintype "passive"))
      (node (ref "T28") (pin "B") (pinfunction "B_B") (pintype "passive"))
    )
    (net (code "44") (name "MA10") (class "Default")
      (node (ref "E40TOP") (pin "15") (pinfunction "1_15") (pintype "passive"))
      (node (ref "F40") (pin "27") (pinfunction "27_27") (pintype "passive"))
      (node (ref "T29") (pin "B") (pinfunction "B_B") (pintype "passive"))
    )
    (net (code "45") (name "MA11") (class "Default")
      (node (ref "E40BOT") (pin "18") (pinfunction "1_18") (pintype "passive"))
      (node (ref "F40") (pin "32") (pinfunction "32_32") (pintype "passive"))
      (node (ref "T30") (pin "B") (pinfunction "B_B") (pintype "passive"))
    )
    (net (code "46") (name "MB0") (class "Default")
      (node (ref "D40TOP") (pin "3") (pinfunction "1_3") (pintype "passive"))
      (node (ref "E40") (pin "5") (pinfunction "5_5") (pintype "passive"))
      (node (ref "T31") (pin "B") (pinfunction "B_B") (pintype "passive"))
    )
    (net (code "47") (name "MB1") (class "Default")
      (node (ref "D40BOT") (pin "3") (pinfunction "1_3") (pintype "passive"))
      (node (ref "E40") (pin "6") (pinfunction "6_6") (pintype "passive"))
      (node (ref "T32") (pin "B") (pinfunction "B_B") (pintype "passive"))
    )
    (net (code "48") (name "MB2") (class "Default")
      (node (ref "D40TOP") (pin "8") (pinfunction "1_8") (pintype "passive"))
      (node (ref "E40") (pin "15") (pinfunction "15_15") (pintype "passive"))
      (node (ref "T33") (pin "B") (pinfunction "B_B") (pintype "passive"))
    )
    (net (code "49") (name "MB3") (class "Default")
      (node (ref "D40BOT") (pin "11") (pinfunction "1_11") (pintype "passive"))
      (node (ref "E40") (pin "16") (pinfunction "16_16") (pintype "passive"))
      (node (ref "T34") (pin "B") (pinfunction "B_B") (pintype "passive"))
    )
    (net (code "50") (name "MB4") (class "Default")
      (node (ref "D40TOP") (pin "16") (pinfunction "1_16") (pintype "passive"))
      (node (ref "E40") (pin "29") (pinfunction "29_29") (pintype "passive"))
      (node (ref "T35") (pin "B") (pinfunction "B_B") (pintype "passive"))
    )
    (net (code "51") (name "MB5") (class "Default")
      (node (ref "D40BOT") (pin "17") (pinfunction "1_17") (pintype "passive"))
      (node (ref "E40") (pin "30") (pinfunction "30_30") (pintype "passive"))
      (node (ref "T36") (pin "B") (pinfunction "B_B") (pintype "passive"))
    )
    (net (code "52") (name "MB6") (class "Default")
      (node (ref "E40TOP") (pin "3") (pinfunction "1_3") (pintype "passive"))
      (node (ref "F40") (pin "5") (pinfunction "5_5") (pintype "passive"))
      (node (ref "T37") (pin "B") (pinfunction "B_B") (pintype "passive"))
    )
    (net (code "53") (name "MB7") (class "Default")
      (node (ref "E40BOT") (pin "3") (pinfunction "1_3") (pintype "passive"))
      (node (ref "F40") (pin "6") (pinfunction "6_6") (pintype "passive"))
      (node (ref "T38") (pin "B") (pinfunction "B_B") (pintype "passive"))
    )
    (net (code "54") (name "MB8") (class "Default")
      (node (ref "E40TOP") (pin "8") (pinfunction "1_8") (pintype "passive"))
      (node (ref "F40") (pin "15") (pinfunction "15_15") (pintype "passive"))
      (node (ref "T39") (pin "B") (pinfunction "B_B") (pintype "passive"))
    )
    (net (code "55") (name "MB9") (class "Default")
      (node (ref "E40BOT") (pin "11") (pinfunction "1_11") (pintype "passive"))
      (node (ref "F40") (pin "16") (pinfunction "16_16") (pintype "passive"))
      (node (ref "T40") (pin "B") (pinfunction "B_B") (pintype "passive"))
    )
    (net (code "56") (name "MB10") (class "Default")
      (node (ref "E40TOP") (pin "16") (pinfunction "1_16") (pintype "passive"))
      (node (ref "F40") (pin "29") (pinfunction "29_29") (pintype "passive"))
      (node (ref "T41") (pin "B") (pinfunction "B_B") (pintype "passive"))
    )
    (net (code "57") (name "MB11") (class "Default")
      (node (ref "E40BOT") (pin "17") (pinfunction "1_17") (pintype "passive"))
      (node (ref "F40") (pin "30") (pinfunction "30_30") (pintype "passive"))
      (node (ref "T42") (pin "B") (pinfunction "B_B") (pintype "passive"))
    )
    (net (code "58") (name "MQ0") (class "Default")
      (node (ref "D40TOP") (pin "5") (pinfunction "1_5") (pintype "passive"))
      (node (ref "E40") (pin "9") (pinfunction "9_9") (pintype "passive"))
      (node (ref "T55") (pin "B") (pinfunction "B_B") (pintype "passive"))
    )
    (net (code "59") (name "MQ1") (class "Default")
      (node (ref "D40BOT") (pin "1") (pinfunction "1_1") (pintype "passive"))
      (node (ref "E40") (pin "2") (pinfunction "2_2") (pintype "passive"))
      (node (ref "T56") (pin "B") (pinfunction "B_B") (pintype "passive"))
    )
    (net (code "60") (name "MQ2") (class "Default")
      (node (ref "D40TOP") (pin "13") (pinfunction "1_13") (pintype "passive"))
      (node (ref "E40") (pin "23") (pinfunction "23_23") (pintype "passive"))
      (node (ref "T57") (pin "B") (pinfunction "B_B") (pintype "passive"))
    )
    (net (code "61") (name "MQ3") (class "Default")
      (node (ref "D40BOT") (pin "6") (pinfunction "1_6") (pintype "passive"))
      (node (ref "E40") (pin "12") (pinfunction "12_12") (pintype "passive"))
      (node (ref "T58") (pin "B") (pinfunction "B_B") (pintype "passive"))
    )
    (net (code "62") (name "MQ4") (class "Default")
      (node (ref "D40TOP") (pin "18") (pinfunction "1_18") (pintype "passive"))
      (node (ref "E40") (pin "33") (pinfunction "33_33") (pintype "passive"))
      (node (ref "T59") (pin "B") (pinfunction "B_B") (pintype "passive"))
    )
    (net (code "63") (name "MQ5") (class "Default")
      (node (ref "D40BOT") (pin "15") (pinfunction "1_15") (pintype "passive"))
      (node (ref "E40") (pin "26") (pinfunction "26_26") (pintype "passive"))
      (node (ref "T60") (pin "B") (pinfunction "B_B") (pintype "passive"))
    )
    (net (code "64") (name "MQ6") (class "Default")
      (node (ref "E40TOP") (pin "5") (pinfunction "1_5") (pintype "passive"))
      (node (ref "F40") (pin "9") (pinfunction "9_9") (pintype "passive"))
      (node (ref "T61") (pin "B") (pinfunction "B_B") (pintype "passive"))
    )
    (net (code "65") (name "MQ7") (class "Default")
      (node (ref "E40BOT") (pin "1") (pinfunction "1_1") (pintype "passive"))
      (node (ref "F40") (pin "2") (pinfunction "2_2") (pintype "passive"))
      (node (ref "T62") (pin "B") (pinfunction "B_B") (pintype "passive"))
    )
    (net (code "66") (name "MQ8") (class "Default")
      (node (ref "E40TOP") (pin "13") (pinfunction "1_13") (pintype "passive"))
      (node (ref "F40") (pin "23") (pinfunction "23_23") (pintype "passive"))
      (node (ref "T63") (pin "B") (pinfunction "B_B") (pintype "passive"))
    )
    (net (code "67") (name "MQ9") (class "Default")
      (node (ref "E40BOT") (pin "6") (pinfunction "1_6") (pintype "passive"))
      (node (ref "F40") (pin "12") (pinfunction "12_12") (pintype "passive"))
      (node (ref "T64") (pin "B") (pinfunction "B_B") (pintype "passive"))
    )
    (net (code "68") (name "MQ10") (class "Default")
      (node (ref "E40TOP") (pin "18") (pinfunction "1_18") (pintype "passive"))
      (node (ref "F40") (pin "33") (pinfunction "33_33") (pintype "passive"))
      (node (ref "T65") (pin "B") (pinfunction "B_B") (pintype "passive"))
    )
    (net (code "69") (name "MQ11") (class "Default")
      (node (ref "E40BOT") (pin "15") (pinfunction "1_15") (pintype "passive"))
      (node (ref "F40") (pin "26") (pinfunction "26_26") (pintype "passive"))
      (node (ref "T66") (pin "B") (pinfunction "B_B") (pintype "passive"))
    )
    (net (code "70") (name "Net-(AC0-PadA)") (class "Default")
      (node (ref "AC0") (pin "A") (pinfunction "A_A") (pintype "passive"))
      (node (ref "R43") (pin "2") (pinfunction "2_2") (pintype "passive"))
    )
    (net (code "71") (name "Net-(AC0-PadB)") (class "Default")
      (node (ref "AC0") (pin "B") (pinfunction "B_B") (pintype "passive"))
      (node (ref "T43") (pin "C") (pinfunction "C_C") (pintype "passive"))
    )
    (net (code "72") (name "Net-(AC1-PadA)") (class "Default")
      (node (ref "AC1") (pin "A") (pinfunction "A_A") (pintype "passive"))
      (node (ref "R44") (pin "2") (pinfunction "2_2") (pintype "passive"))
    )
    (net (code "73") (name "Net-(AC1-PadB)") (class "Default")
      (node (ref "AC1") (pin "B") (pinfunction "B_B") (pintype "passive"))
      (node (ref "T44") (pin "C") (pinfunction "C_C") (pintype "passive"))
    )
    (net (code "74") (name "Net-(AC2-PadA)") (class "Default")
      (node (ref "AC2") (pin "A") (pinfunction "A_A") (pintype "passive"))
      (node (ref "R45") (pin "2") (pinfunction "2_2") (pintype "passive"))
    )
    (net (code "75") (name "Net-(AC2-PadB)") (class "Default")
      (node (ref "AC2") (pin "B") (pinfunction "B_B") (pintype "passive"))
      (node (ref "T45") (pin "C") (pinfunction "C_C") (pintype "passive"))
    )
    (net (code "76") (name "Net-(AC3-PadA)") (class "Default")
      (node (ref "AC3") (pin "A") (pinfunction "A_A") (pintype "passive"))
      (node (ref "R46") (pin "2") (pinfunction "2_2") (pintype "passive"))
    )
    (net (code "77") (name "Net-(AC3-PadB)") (class "Default")
      (node (ref "AC3") (pin "B") (pinfunction "B_B") (pintype "passive"))
      (node (ref "T46") (pin "C") (pinfunction "C_C") (pintype "passive"))
    )
    (net (code "78") (name "Net-(AC4-PadA)") (class "Default")
      (node (ref "AC4") (pin "A") (pinfunction "A_A") (pintype "passive"))
      (node (ref "R47") (pin "2") (pinfunction "2_2") (pintype "passive"))
    )
    (net (code "79") (name "Net-(AC4-PadB)") (class "Default")
      (node (ref "AC4") (pin "B") (pinfunction "B_B") (pintype "passive"))
      (node (ref "T47") (pin "C") (pinfunction "C_C") (pintype "passive"))
    )
    (net (code "80") (name "Net-(AC5-PadA)") (class "Default")
      (node (ref "AC5") (pin "A") (pinfunction "A_A") (pintype "passive"))
      (node (ref "R48") (pin "2") (pinfunction "2_2") (pintype "passive"))
    )
    (net (code "81") (name "Net-(AC5-PadB)") (class "Default")
      (node (ref "AC5") (pin "B") (pinfunction "B_B") (pintype "passive"))
      (node (ref "T48") (pin "C") (pinfunction "C_C") (pintype "passive"))
    )
    (net (code "82") (name "Net-(AC6-PadA)") (class "Default")
      (node (ref "AC6") (pin "A") (pinfunction "A_A") (pintype "passive"))
      (node (ref "R49") (pin "2") (pinfunction "2_2") (pintype "passive"))
    )
    (net (code "83") (name "Net-(AC6-PadB)") (class "Default")
      (node (ref "AC6") (pin "B") (pinfunction "B_B") (pintype "passive"))
      (node (ref "T49") (pin "C") (pinfunction "C_C") (pintype "passive"))
    )
    (net (code "84") (name "Net-(AC7-PadA)") (class "Default")
      (node (ref "AC7") (pin "A") (pinfunction "A_A") (pintype "passive"))
      (node (ref "R50") (pin "2") (pinfunction "2_2") (pintype "passive"))
    )
    (net (code "85") (name "Net-(AC7-PadB)") (class "Default")
      (node (ref "AC7") (pin "B") (pinfunction "B_B") (pintype "passive"))
      (node (ref "T50") (pin "C") (pinfunction "C_C") (pintype "passive"))
    )
    (net (code "86") (name "Net-(AC8-PadA)") (class "Default")
      (node (ref "AC8") (pin "A") (pinfunction "A_A") (pintype "passive"))
      (node (ref "R51") (pin "2") (pinfunction "2_2") (pintype "passive"))
    )
    (net (code "87") (name "Net-(AC8-PadB)") (class "Default")
      (node (ref "AC8") (pin "B") (pinfunction "B_B") (pintype "passive"))
      (node (ref "T51") (pin "C") (pinfunction "C_C") (pintype "passive"))
    )
    (net (code "88") (name "Net-(AC9-PadA)") (class "Default")
      (node (ref "AC9") (pin "A") (pinfunction "A_A") (pintype "passive"))
      (node (ref "R52") (pin "2") (pinfunction "2_2") (pintype "passive"))
    )
    (net (code "89") (name "Net-(AC9-PadB)") (class "Default")
      (node (ref "AC9") (pin "B") (pinfunction "B_B") (pintype "passive"))
      (node (ref "T52") (pin "C") (pinfunction "C_C") (pintype "passive"))
    )
    (net (code "90") (name "Net-(AC10-PadA)") (class "Default")
      (node (ref "AC10") (pin "A") (pinfunction "A_A") (pintype "passive"))
      (node (ref "R53") (pin "2") (pinfunction "2_2") (pintype "passive"))
    )
    (net (code "91") (name "Net-(AC10-PadB)") (class "Default")
      (node (ref "AC10") (pin "B") (pinfunction "B_B") (pintype "passive"))
      (node (ref "T53") (pin "C") (pinfunction "C_C") (pintype "passive"))
    )
    (net (code "92") (name "Net-(AC11-PadA)") (class "Default")
      (node (ref "AC11") (pin "A") (pinfunction "A_A") (pintype "passive"))
      (node (ref "R54") (pin "2") (pinfunction "2_2") (pintype "passive"))
    )
    (net (code "93") (name "Net-(AC11-PadB)") (class "Default")
      (node (ref "AC11") (pin "B") (pinfunction "B_B") (pintype "passive"))
      (node (ref "T54") (pin "C") (pinfunction "C_C") (pintype "passive"))
    )
    (net (code "94") (name "Net-(AND-PadA)") (class "Default")
      (node (ref "AND") (pin "A") (pinfunction "A_A") (pintype "passive"))
      (node (ref "R82") (pin "2") (pinfunction "2_2") (pintype "passive"))
    )
    (net (code "95") (name "Net-(AND-PadB)") (class "Default")
      (node (ref "AND") (pin "B") (pinfunction "B_B") (pintype "passive"))
      (node (ref "T82") (pin "C") (pinfunction "C_C") (pintype "passive"))
    )
    (net (code "96") (name "Net-(BREAK-PadA)") (class "Default")
      (node (ref "BREAK") (pin "A") (pinfunction "A_A") (pintype "passive"))
      (node (ref "R81") (pin "2") (pinfunction "2_2") (pintype "passive"))
    )
    (net (code "97") (name "Net-(BREAK-PadB)") (class "Default")
      (node (ref "BREAK") (pin "B") (pinfunction "B_B") (pintype "passive"))
      (node (ref "T81") (pin "C") (pinfunction "C_C") (pintype "passive"))
    )
    (net (code "98") (name "Net-(CURRENTADDRESS-PadA)") (class "Default")
      (node (ref "CURRENTADDRESS") (pin "A") (pinfunction "A_A") (pintype "passive"))
      (node (ref "R80") (pin "2") (pinfunction "2_2") (pintype "passive"))
    )
    (net (code "99") (name "Net-(CURRENTADDRESS-PadB)") (class "Default")
      (node (ref "CURRENTADDRESS") (pin "B") (pinfunction "B_B") (pintype "passive"))
      (node (ref "T80") (pin "C") (pinfunction "C_C") (pintype "passive"))
    )
    (net (code "100") (name "Net-(DCA-PadA)") (class "Default")
      (node (ref "DCA") (pin "A") (pinfunction "A_A") (pintype "passive"))
      (node (ref "R85") (pin "2") (pinfunction "2_2") (pintype "passive"))
    )
    (net (code "101") (name "Net-(DCA-PadB)") (class "Default")
      (node (ref "DCA") (pin "B") (pinfunction "B_B") (pintype "passive"))
      (node (ref "T85") (pin "C") (pinfunction "C_C") (pintype "passive"))
    )
    (net (code "102") (name "Net-(DEFER-PadA)") (class "Default")
      (node (ref "DEFER") (pin "A") (pinfunction "A_A") (pintype "passive"))
      (node (ref "R78") (pin "2") (pinfunction "2_2") (pintype "passive"))
    )
    (net (code "103") (name "Net-(DEFER-PadB)") (class "Default")
      (node (ref "DEFER") (pin "B") (pinfunction "B_B") (pintype "passive"))
      (node (ref "T78") (pin "C") (pinfunction "C_C") (pintype "passive"))
    )
    (net (code "104") (name "Net-(DF0-PadA)") (class "Default")
      (node (ref "DF0") (pin "A") (pinfunction "A_A") (pintype "passive"))
      (node (ref "R1") (pin "2") (pinfunction "2_2") (pintype "passive"))
    )
    (net (code "105") (name "Net-(DF0-PadB)") (class "Default")
      (node (ref "DF0") (pin "B") (pinfunction "B_B") (pintype "passive"))
      (node (ref "T1") (pin "C") (pinfunction "C_C") (pintype "passive"))
    )
    (net (code "106") (name "Net-(DF1-PadA)") (class "Default")
      (node (ref "DF1") (pin "A") (pinfunction "A_A") (pintype "passive"))
      (node (ref "R2") (pin "2") (pinfunction "2_2") (pintype "passive"))
    )
    (net (code "107") (name "Net-(DF1-PadB)") (class "Default")
      (node (ref "DF1") (pin "B") (pinfunction "B_B") (pintype "passive"))
      (node (ref "T2") (pin "C") (pinfunction "C_C") (pintype "passive"))
    )
    (net (code "108") (name "Net-(DF2-PadA)") (class "Default")
      (node (ref "DF2") (pin "A") (pinfunction "A_A") (pintype "passive"))
      (node (ref "R3") (pin "2") (pinfunction "2_2") (pintype "passive"))
    )
    (net (code "109") (name "Net-(DF2-PadB)") (class "Default")
      (node (ref "DF2") (pin "B") (pinfunction "B_B") (pintype "passive"))
      (node (ref "T3") (pin "C") (pinfunction "C_C") (pintype "passive"))
    )
    (net (code "110") (name "Net-(EXECUTE-PadA)") (class "Default")
      (node (ref "EXECUTE") (pin "A") (pinfunction "A_A") (pintype "passive"))
      (node (ref "R77") (pin "2") (pinfunction "2_2") (pintype "passive"))
    )
    (net (code "111") (name "Net-(EXECUTE-PadB)") (class "Default")
      (node (ref "EXECUTE") (pin "B") (pinfunction "B_B") (pintype "passive"))
      (node (ref "T77") (pin "C") (pinfunction "C_C") (pintype "passive"))
    )
    (net (code "112") (name "Net-(FETCH-PadA)") (class "Default")
      (node (ref "FETCH") (pin "A") (pinfunction "A_A") (pintype "passive"))
      (node (ref "R76") (pin "2") (pinfunction "2_2") (pintype "passive"))
    )
    (net (code "113") (name "Net-(FETCH-PadB)") (class "Default")
      (node (ref "FETCH") (pin "B") (pinfunction "B_B") (pintype "passive"))
      (node (ref "T76") (pin "C") (pinfunction "C_C") (pintype "passive"))
    )
    (net (code "114") (name "Net-(IF0-PadA)") (class "Default")
      (node (ref "IF0") (pin "A") (pinfunction "A_A") (pintype "passive"))
      (node (ref "R4") (pin "2") (pinfunction "2_2") (pintype "passive"))
    )
    (net (code "115") (name "Net-(IF0-PadB)") (class "Default")
      (node (ref "IF0") (pin "B") (pinfunction "B_B") (pintype "passive"))
      (node (ref "T4") (pin "C") (pinfunction "C_C") (pintype "passive"))
    )
    (net (code "116") (name "Net-(IF1-PadA)") (class "Default")
      (node (ref "IF1") (pin "A") (pinfunction "A_A") (pintype "passive"))
      (node (ref "R5") (pin "2") (pinfunction "2_2") (pintype "passive"))
    )
    (net (code "117") (name "Net-(IF1-PadB)") (class "Default")
      (node (ref "IF1") (pin "B") (pinfunction "B_B") (pintype "passive"))
      (node (ref "T5") (pin "C") (pinfunction "C_C") (pintype "passive"))
    )
    (net (code "118") (name "Net-(IF2-PadA)") (class "Default")
      (node (ref "IF2") (pin "A") (pinfunction "A_A") (pintype "passive"))
      (node (ref "R6") (pin "2") (pinfunction "2_2") (pintype "passive"))
    )
    (net (code "119") (name "Net-(IF2-PadB)") (class "Default")
      (node (ref "IF2") (pin "B") (pinfunction "B_B") (pintype "passive"))
      (node (ref "T6") (pin "C") (pinfunction "C_C") (pintype "passive"))
    )
    (net (code "120") (name "Net-(ION-PadA)") (class "Default")
      (node (ref "ION") (pin "A") (pinfunction "A_A") (pintype "passive"))
      (node (ref "R73") (pin "2") (pinfunction "2_2") (pintype "passive"))
    )
    (net (code "121") (name "Net-(ION-PadB)") (class "Default")
      (node (ref "ION") (pin "B") (pinfunction "B_B") (pintype "passive"))
      (node (ref "T73") (pin "C") (pinfunction "C_C") (pintype "passive"))
    )
    (net (code "122") (name "Net-(IOT-PadA)") (class "Default")
      (node (ref "IOT") (pin "A") (pinfunction "A_A") (pintype "passive"))
      (node (ref "R88") (pin "2") (pinfunction "2_2") (pintype "passive"))
    )
    (net (code "123") (name "Net-(IOT-PadB)") (class "Default")
      (node (ref "IOT") (pin "B") (pinfunction "B_B") (pintype "passive"))
      (node (ref "T88") (pin "C") (pinfunction "C_C") (pintype "passive"))
    )
    (net (code "124") (name "Net-(ISZ-PadA)") (class "Default")
      (node (ref "ISZ") (pin "A") (pinfunction "A_A") (pintype "passive"))
      (node (ref "R84") (pin "2") (pinfunction "2_2") (pintype "passive"))
    )
    (net (code "125") (name "Net-(ISZ-PadB)") (class "Default")
      (node (ref "ISZ") (pin "B") (pinfunction "B_B") (pintype "passive"))
      (node (ref "T84") (pin "C") (pinfunction "C_C") (pintype "passive"))
    )
    (net (code "126") (name "Net-(JMP-PadA)") (class "Default")
      (node (ref "JMP") (pin "A") (pinfunction "A_A") (pintype "passive"))
      (node (ref "R87") (pin "2") (pinfunction "2_2") (pintype "passive"))
    )
    (net (code "127") (name "Net-(JMP-PadB)") (class "Default")
      (node (ref "JMP") (pin "B") (pinfunction "B_B") (pintype "passive"))
      (node (ref "T87") (pin "C") (pinfunction "C_C") (pintype "passive"))
    )
    (net (code "128") (name "Net-(JMS-PadA)") (class "Default")
      (node (ref "JMS") (pin "A") (pinfunction "A_A") (pintype "passive"))
      (node (ref "R86") (pin "2") (pinfunction "2_2") (pintype "passive"))
    )
    (net (code "129") (name "Net-(JMS-PadB)") (class "Default")
      (node (ref "JMS") (pin "B") (pinfunction "B_B") (pintype "passive"))
      (node (ref "T86") (pin "C") (pinfunction "C_C") (pintype "passive"))
    )
    (net (code "130") (name "Net-(LINK-PadA)") (class "Default")
      (node (ref "LINK") (pin "A") (pinfunction "A_A") (pintype "passive"))
      (node (ref "R72") (pin "2") (pinfunction "2_2") (pintype "passive"))
    )
    (net (code "131") (name "Net-(LINK-PadB)") (class "Default")
      (node (ref "LINK") (pin "B") (pinfunction "B_B") (pintype "passive"))
      (node (ref "T72") (pin "C") (pinfunction "C_C") (pintype "passive"))
    )
    (net (code "132") (name "Net-(MA0-PadA)") (class "Default")
      (node (ref "MA0") (pin "A") (pinfunction "A_A") (pintype "passive"))
      (node (ref "R19") (pin "2") (pinfunction "2_2") (pintype "passive"))
    )
    (net (code "133") (name "Net-(MA0-PadB)") (class "Default")
      (node (ref "MA0") (pin "B") (pinfunction "B_B") (pintype "passive"))
      (node (ref "T19") (pin "C") (pinfunction "C_C") (pintype "passive"))
    )
    (net (code "134") (name "Net-(MA1-PadA)") (class "Default")
      (node (ref "MA1") (pin "A") (pinfunction "A_A") (pintype "passive"))
      (node (ref "R20") (pin "2") (pinfunction "2_2") (pintype "passive"))
    )
    (net (code "135") (name "Net-(MA1-PadB)") (class "Default")
      (node (ref "MA1") (pin "B") (pinfunction "B_B") (pintype "passive"))
      (node (ref "T20") (pin "C") (pinfunction "C_C") (pintype "passive"))
    )
    (net (code "136") (name "Net-(MA2-PadA)") (class "Default")
      (node (ref "MA2") (pin "A") (pinfunction "A_A") (pintype "passive"))
      (node (ref "R21") (pin "2") (pinfunction "2_2") (pintype "passive"))
    )
    (net (code "137") (name "Net-(MA2-PadB)") (class "Default")
      (node (ref "MA2") (pin "B") (pinfunction "B_B") (pintype "passive"))
      (node (ref "T21") (pin "C") (pinfunction "C_C") (pintype "passive"))
    )
    (net (code "138") (name "Net-(MA3-PadA)") (class "Default")
      (node (ref "MA3") (pin "A") (pinfunction "A_A") (pintype "passive"))
      (node (ref "R22") (pin "2") (pinfunction "2_2") (pintype "passive"))
    )
    (net (code "139") (name "Net-(MA3-PadB)") (class "Default")
      (node (ref "MA3") (pin "B") (pinfunction "B_B") (pintype "passive"))
      (node (ref "T22") (pin "C") (pinfunction "C_C") (pintype "passive"))
    )
    (net (code "140") (name "Net-(MA4-PadA)") (class "Default")
      (node (ref "MA4") (pin "A") (pinfunction "A_A") (pintype "passive"))
      (node (ref "R23") (pin "2") (pinfunction "2_2") (pintype "passive"))
    )
    (net (code "141") (name "Net-(MA4-PadB)") (class "Default")
      (node (ref "MA4") (pin "B") (pinfunction "B_B") (pintype "passive"))
      (node (ref "T23") (pin "C") (pinfunction "C_C") (pintype "passive"))
    )
    (net (code "142") (name "Net-(MA5-PadA)") (class "Default")
      (node (ref "MA5") (pin "A") (pinfunction "A_A") (pintype "passive"))
      (node (ref "R24") (pin "2") (pinfunction "2_2") (pintype "passive"))
    )
    (net (code "143") (name "Net-(MA5-PadB)") (class "Default")
      (node (ref "MA5") (pin "B") (pinfunction "B_B") (pintype "passive"))
      (node (ref "T24") (pin "C") (pinfunction "C_C") (pintype "passive"))
    )
    (net (code "144") (name "Net-(MA6-PadA)") (class "Default")
      (node (ref "MA6") (pin "A") (pinfunction "A_A") (pintype "passive"))
      (node (ref "R25") (pin "2") (pinfunction "2_2") (pintype "passive"))
    )
    (net (code "145") (name "Net-(MA6-PadB)") (class "Default")
      (node (ref "MA6") (pin "B") (pinfunction "B_B") (pintype "passive"))
      (node (ref "T25") (pin "C") (pinfunction "C_C") (pintype "passive"))
    )
    (net (code "146") (name "Net-(MA7-PadA)") (class "Default")
      (node (ref "MA7") (pin "A") (pinfunction "A_A") (pintype "passive"))
      (node (ref "R26") (pin "2") (pinfunction "2_2") (pintype "passive"))
    )
    (net (code "147") (name "Net-(MA7-PadB)") (class "Default")
      (node (ref "MA7") (pin "B") (pinfunction "B_B") (pintype "passive"))
      (node (ref "T26") (pin "C") (pinfunction "C_C") (pintype "passive"))
    )
    (net (code "148") (name "Net-(MA8-PadA)") (class "Default")
      (node (ref "MA8") (pin "A") (pinfunction "A_A") (pintype "passive"))
      (node (ref "R27") (pin "2") (pinfunction "2_2") (pintype "passive"))
    )
    (net (code "149") (name "Net-(MA8-PadB)") (class "Default")
      (node (ref "MA8") (pin "B") (pinfunction "B_B") (pintype "passive"))
      (node (ref "T27") (pin "C") (pinfunction "C_C") (pintype "passive"))
    )
    (net (code "150") (name "Net-(MA9-PadA)") (class "Default")
      (node (ref "MA9") (pin "A") (pinfunction "A_A") (pintype "passive"))
      (node (ref "R28") (pin "2") (pinfunction "2_2") (pintype "passive"))
    )
    (net (code "151") (name "Net-(MA9-PadB)") (class "Default")
      (node (ref "MA9") (pin "B") (pinfunction "B_B") (pintype "passive"))
      (node (ref "T28") (pin "C") (pinfunction "C_C") (pintype "passive"))
    )
    (net (code "152") (name "Net-(MA10-PadA)") (class "Default")
      (node (ref "MA10") (pin "A") (pinfunction "A_A") (pintype "passive"))
      (node (ref "R29") (pin "2") (pinfunction "2_2") (pintype "passive"))
    )
    (net (code "153") (name "Net-(MA10-PadB)") (class "Default")
      (node (ref "MA10") (pin "B") (pinfunction "B_B") (pintype "passive"))
      (node (ref "T29") (pin "C") (pinfunction "C_C") (pintype "passive"))
    )
    (net (code "154") (name "Net-(MA11-PadA)") (class "Default")
      (node (ref "MA11") (pin "A") (pinfunction "A_A") (pintype "passive"))
      (node (ref "R30") (pin "2") (pinfunction "2_2") (pintype "passive"))
    )
    (net (code "155") (name "Net-(MA11-PadB)") (class "Default")
      (node (ref "MA11") (pin "B") (pinfunction "B_B") (pintype "passive"))
      (node (ref "T30") (pin "C") (pinfunction "C_C") (pintype "passive"))
    )
    (net (code "156") (name "Net-(MB0-PadA)") (class "Default")
      (node (ref "MB0") (pin "A") (pinfunction "A_A") (pintype "passive"))
      (node (ref "R31") (pin "2") (pinfunction "2_2") (pintype "passive"))
    )
    (net (code "157") (name "Net-(MB0-PadB)") (class "Default")
      (node (ref "MB0") (pin "B") (pinfunction "B_B") (pintype "passive"))
      (node (ref "T31") (pin "C") (pinfunction "C_C") (pintype "passive"))
    )
    (net (code "158") (name "Net-(MB1-PadA)") (class "Default")
      (node (ref "MB1") (pin "A") (pinfunction "A_A") (pintype "passive"))
      (node (ref "R32") (pin "2") (pinfunction "2_2") (pintype "passive"))
    )
    (net (code "159") (name "Net-(MB1-PadB)") (class "Default")
      (node (ref "MB1") (pin "B") (pinfunction "B_B") (pintype "passive"))
      (node (ref "T32") (pin "C") (pinfunction "C_C") (pintype "passive"))
    )
    (net (code "160") (name "Net-(MB2-PadA)") (class "Default")
      (node (ref "MB2") (pin "A") (pinfunction "A_A") (pintype "passive"))
      (node (ref "R33") (pin "2") (pinfunction "2_2") (pintype "passive"))
    )
    (net (code "161") (name "Net-(MB2-PadB)") (class "Default")
      (node (ref "MB2") (pin "B") (pinfunction "B_B") (pintype "passive"))
      (node (ref "T33") (pin "C") (pinfunction "C_C") (pintype "passive"))
    )
    (net (code "162") (name "Net-(MB3-PadA)") (class "Default")
      (node (ref "MB3") (pin "A") (pinfunction "A_A") (pintype "passive"))
      (node (ref "R34") (pin "2") (pinfunction "2_2") (pintype "passive"))
    )
    (net (code "163") (name "Net-(MB3-PadB)") (class "Default")
      (node (ref "MB3") (pin "B") (pinfunction "B_B") (pintype "passive"))
      (node (ref "T34") (pin "C") (pinfunction "C_C") (pintype "passive"))
    )
    (net (code "164") (name "Net-(MB4-PadA)") (class "Default")
      (node (ref "MB4") (pin "A") (pinfunction "A_A") (pintype "passive"))
      (node (ref "R35") (pin "2") (pinfunction "2_2") (pintype "passive"))
    )
    (net (code "165") (name "Net-(MB4-PadB)") (class "Default")
      (node (ref "MB4") (pin "B") (pinfunction "B_B") (pintype "passive"))
      (node (ref "T35") (pin "C") (pinfunction "C_C") (pintype "passive"))
    )
    (net (code "166") (name "Net-(MB5-PadA)") (class "Default")
      (node (ref "MB5") (pin "A") (pinfunction "A_A") (pintype "passive"))
      (node (ref "R36") (pin "2") (pinfunction "2_2") (pintype "passive"))
    )
    (net (code "167") (name "Net-(MB5-PadB)") (class "Default")
      (node (ref "MB5") (pin "B") (pinfunction "B_B") (pintype "passive"))
      (node (ref "T36") (pin "C") (pinfunction "C_C") (pintype "passive"))
    )
    (net (code "168") (name "Net-(MB6-PadA)") (class "Default")
      (node (ref "MB6") (pin "A") (pinfunction "A_A") (pintype "passive"))
      (node (ref "R37") (pin "2") (pinfunction "2_2") (pintype "passive"))
    )
    (net (code "169") (name "Net-(MB6-PadB)") (class "Default")
      (node (ref "MB6") (pin "B") (pinfunction "B_B") (pintype "passive"))
      (node (ref "T37") (pin "C") (pinfunction "C_C") (pintype "passive"))
    )
    (net (code "170") (name "Net-(MB7-PadA)") (class "Default")
      (node (ref "MB7") (pin "A") (pinfunction "A_A") (pintype "passive"))
      (node (ref "R38") (pin "2") (pinfunction "2_2") (pintype "passive"))
    )
    (net (code "171") (name "Net-(MB7-PadB)") (class "Default")
      (node (ref "MB7") (pin "B") (pinfunction "B_B") (pintype "passive"))
      (node (ref "T38") (pin "C") (pinfunction "C_C") (pintype "passive"))
    )
    (net (code "172") (name "Net-(MB8-PadA)") (class "Default")
      (node (ref "MB8") (pin "A") (pinfunction "A_A") (pintype "passive"))
      (node (ref "R39") (pin "2") (pinfunction "2_2") (pintype "passive"))
    )
    (net (code "173") (name "Net-(MB8-PadB)") (class "Default")
      (node (ref "MB8") (pin "B") (pinfunction "B_B") (pintype "passive"))
      (node (ref "T39") (pin "C") (pinfunction "C_C") (pintype "passive"))
    )
    (net (code "174") (name "Net-(MB9-PadA)") (class "Default")
      (node (ref "MB9") (pin "A") (pinfunction "A_A") (pintype "passive"))
      (node (ref "R40") (pin "2") (pinfunction "2_2") (pintype "passive"))
    )
    (net (code "175") (name "Net-(MB9-PadB)") (class "Default")
      (node (ref "MB9") (pin "B") (pinfunction "B_B") (pintype "passive"))
      (node (ref "T40") (pin "C") (pinfunction "C_C") (pintype "passive"))
    )
    (net (code "176") (name "Net-(MB10-PadA)") (class "Default")
      (node (ref "MB10") (pin "A") (pinfunction "A_A") (pintype "passive"))
      (node (ref "R41") (pin "2") (pinfunction "2_2") (pintype "passive"))
    )
    (net (code "177") (name "Net-(MB10-PadB)") (class "Default")
      (node (ref "MB10") (pin "B") (pinfunction "B_B") (pintype "passive"))
      (node (ref "T41") (pin "C") (pinfunction "C_C") (pintype "passive"))
    )
    (net (code "178") (name "Net-(MB11-PadA)") (class "Default")
      (node (ref "MB11") (pin "A") (pinfunction "A_A") (pintype "passive"))
      (node (ref "R42") (pin "2") (pinfunction "2_2") (pintype "passive"))
    )
    (net (code "179") (name "Net-(MB11-PadB)") (class "Default")
      (node (ref "MB11") (pin "B") (pinfunction "B_B") (pintype "passive"))
      (node (ref "T42") (pin "C") (pinfunction "C_C") (pintype "passive"))
    )
    (net (code "180") (name "Net-(MQ0-PadA)") (class "Default")
      (node (ref "MQ0") (pin "A") (pinfunction "A_A") (pintype "passive"))
      (node (ref "R55") (pin "2") (pinfunction "2_2") (pintype "passive"))
    )
    (net (code "181") (name "Net-(MQ0-PadB)") (class "Default")
      (node (ref "MQ0") (pin "B") (pinfunction "B_B") (pintype "passive"))
      (node (ref "T55") (pin "C") (pinfunction "C_C") (pintype "passive"))
    )
    (net (code "182") (name "Net-(MQ1-PadA)") (class "Default")
      (node (ref "MQ1") (pin "A") (pinfunction "A_A") (pintype "passive"))
      (node (ref "R56") (pin "2") (pinfunction "2_2") (pintype "passive"))
    )
    (net (code "183") (name "Net-(MQ1-PadB)") (class "Default")
      (node (ref "MQ1") (pin "B") (pinfunction "B_B") (pintype "passive"))
      (node (ref "T56") (pin "C") (pinfunction "C_C") (pintype "passive"))
    )
    (net (code "184") (name "Net-(MQ2-PadA)") (class "Default")
      (node (ref "MQ2") (pin "A") (pinfunction "A_A") (pintype "passive"))
      (node (ref "R57") (pin "2") (pinfunction "2_2") (pintype "passive"))
    )
    (net (code "185") (name "Net-(MQ2-PadB)") (class "Default")
      (node (ref "MQ2") (pin "B") (pinfunction "B_B") (pintype "passive"))
      (node (ref "T57") (pin "C") (pinfunction "C_C") (pintype "passive"))
    )
    (net (code "186") (name "Net-(MQ3-PadA)") (class "Default")
      (node (ref "MQ3") (pin "A") (pinfunction "A_A") (pintype "passive"))
      (node (ref "R58") (pin "2") (pinfunction "2_2") (pintype "passive"))
    )
    (net (code "187") (name "Net-(MQ3-PadB)") (class "Default")
      (node (ref "MQ3") (pin "B") (pinfunction "B_B") (pintype "passive"))
      (node (ref "T58") (pin "C") (pinfunction "C_C") (pintype "passive"))
    )
    (net (code "188") (name "Net-(MQ4-PadA)") (class "Default")
      (node (ref "MQ4") (pin "A") (pinfunction "A_A") (pintype "passive"))
      (node (ref "R59") (pin "2") (pinfunction "2_2") (pintype "passive"))
    )
    (net (code "189") (name "Net-(MQ4-PadB)") (class "Default")
      (node (ref "MQ4") (pin "B") (pinfunction "B_B") (pintype "passive"))
      (node (ref "T59") (pin "C") (pinfunction "C_C") (pintype "passive"))
    )
    (net (code "190") (name "Net-(MQ5-PadA)") (class "Default")
      (node (ref "MQ5") (pin "A") (pinfunction "A_A") (pintype "passive"))
      (node (ref "R60") (pin "2") (pinfunction "2_2") (pintype "passive"))
    )
    (net (code "191") (name "Net-(MQ5-PadB)") (class "Default")
      (node (ref "MQ5") (pin "B") (pinfunction "B_B") (pintype "passive"))
      (node (ref "T60") (pin "C") (pinfunction "C_C") (pintype "passive"))
    )
    (net (code "192") (name "Net-(MQ6-PadA)") (class "Default")
      (node (ref "MQ6") (pin "A") (pinfunction "A_A") (pintype "passive"))
      (node (ref "R61") (pin "2") (pinfunction "2_2") (pintype "passive"))
    )
    (net (code "193") (name "Net-(MQ6-PadB)") (class "Default")
      (node (ref "MQ6") (pin "B") (pinfunction "B_B") (pintype "passive"))
      (node (ref "T61") (pin "C") (pinfunction "C_C") (pintype "passive"))
    )
    (net (code "194") (name "Net-(MQ7-PadA)") (class "Default")
      (node (ref "MQ7") (pin "A") (pinfunction "A_A") (pintype "passive"))
      (node (ref "R62") (pin "2") (pinfunction "2_2") (pintype "passive"))
    )
    (net (code "195") (name "Net-(MQ7-PadB)") (class "Default")
      (node (ref "MQ7") (pin "B") (pinfunction "B_B") (pintype "passive"))
      (node (ref "T62") (pin "C") (pinfunction "C_C") (pintype "passive"))
    )
    (net (code "196") (name "Net-(MQ8-PadA)") (class "Default")
      (node (ref "MQ8") (pin "A") (pinfunction "A_A") (pintype "passive"))
      (node (ref "R63") (pin "2") (pinfunction "2_2") (pintype "passive"))
    )
    (net (code "197") (name "Net-(MQ8-PadB)") (class "Default")
      (node (ref "MQ8") (pin "B") (pinfunction "B_B") (pintype "passive"))
      (node (ref "T63") (pin "C") (pinfunction "C_C") (pintype "passive"))
    )
    (net (code "198") (name "Net-(MQ9-PadA)") (class "Default")
      (node (ref "MQ9") (pin "A") (pinfunction "A_A") (pintype "passive"))
      (node (ref "R64") (pin "2") (pinfunction "2_2") (pintype "passive"))
    )
    (net (code "199") (name "Net-(MQ9-PadB)") (class "Default")
      (node (ref "MQ9") (pin "B") (pinfunction "B_B") (pintype "passive"))
      (node (ref "T64") (pin "C") (pinfunction "C_C") (pintype "passive"))
    )
    (net (code "200") (name "Net-(MQ10-PadA)") (class "Default")
      (node (ref "MQ10") (pin "A") (pinfunction "A_A") (pintype "passive"))
      (node (ref "R65") (pin "2") (pinfunction "2_2") (pintype "passive"))
    )
    (net (code "201") (name "Net-(MQ10-PadB)") (class "Default")
      (node (ref "MQ10") (pin "B") (pinfunction "B_B") (pintype "passive"))
      (node (ref "T65") (pin "C") (pinfunction "C_C") (pintype "passive"))
    )
    (net (code "202") (name "Net-(MQ11-PadA)") (class "Default")
      (node (ref "MQ11") (pin "A") (pinfunction "A_A") (pintype "passive"))
      (node (ref "R66") (pin "2") (pinfunction "2_2") (pintype "passive"))
    )
    (net (code "203") (name "Net-(MQ11-PadB)") (class "Default")
      (node (ref "MQ11") (pin "B") (pinfunction "B_B") (pintype "passive"))
      (node (ref "T66") (pin "C") (pinfunction "C_C") (pintype "passive"))
    )
    (net (code "204") (name "Net-(OPR-PadA)") (class "Default")
      (node (ref "OPR") (pin "A") (pinfunction "A_A") (pintype "passive"))
      (node (ref "R89") (pin "2") (pinfunction "2_2") (pintype "passive"))
    )
    (net (code "205") (name "Net-(OPR-PadB)") (class "Default")
      (node (ref "OPR") (pin "B") (pinfunction "B_B") (pintype "passive"))
      (node (ref "T89") (pin "C") (pinfunction "C_C") (pintype "passive"))
    )
    (net (code "206") (name "Net-(PAUSE-PadA)") (class "Default")
      (node (ref "PAUSE") (pin "A") (pinfunction "A_A") (pintype "passive"))
      (node (ref "R74") (pin "2") (pinfunction "2_2") (pintype "passive"))
    )
    (net (code "207") (name "Net-(PAUSE-PadB)") (class "Default")
      (node (ref "PAUSE") (pin "B") (pinfunction "B_B") (pintype "passive"))
      (node (ref "T74") (pin "C") (pinfunction "C_C") (pintype "passive"))
    )
    (net (code "208") (name "Net-(PC0-PadA)") (class "Default")
      (node (ref "PC0") (pin "A") (pinfunction "A_A") (pintype "passive"))
      (node (ref "R7") (pin "2") (pinfunction "2_2") (pintype "passive"))
    )
    (net (code "209") (name "Net-(PC0-PadB)") (class "Default")
      (node (ref "PC0") (pin "B") (pinfunction "B_B") (pintype "passive"))
      (node (ref "T7") (pin "C") (pinfunction "C_C") (pintype "passive"))
    )
    (net (code "210") (name "Net-(PC1-PadA)") (class "Default")
      (node (ref "PC1") (pin "A") (pinfunction "A_A") (pintype "passive"))
      (node (ref "R8") (pin "2") (pinfunction "2_2") (pintype "passive"))
    )
    (net (code "211") (name "Net-(PC1-PadB)") (class "Default")
      (node (ref "PC1") (pin "B") (pinfunction "B_B") (pintype "passive"))
      (node (ref "T8") (pin "C") (pinfunction "C_C") (pintype "passive"))
    )
    (net (code "212") (name "Net-(PC2-PadA)") (class "Default")
      (node (ref "PC2") (pin "A") (pinfunction "A_A") (pintype "passive"))
      (node (ref "R9") (pin "2") (pinfunction "2_2") (pintype "passive"))
    )
    (net (code "213") (name "Net-(PC2-PadB)") (class "Default")
      (node (ref "PC2") (pin "B") (pinfunction "B_B") (pintype "passive"))
      (node (ref "T9") (pin "C") (pinfunction "C_C") (pintype "passive"))
    )
    (net (code "214") (name "Net-(PC3-PadA)") (class "Default")
      (node (ref "PC3") (pin "A") (pinfunction "A_A") (pintype "passive"))
      (node (ref "R10") (pin "2") (pinfunction "2_2") (pintype "passive"))
    )
    (net (code "215") (name "Net-(PC3-PadB)") (class "Default")
      (node (ref "PC3") (pin "B") (pinfunction "B_B") (pintype "passive"))
      (node (ref "T10") (pin "C") (pinfunction "C_C") (pintype "passive"))
    )
    (net (code "216") (name "Net-(PC4-PadA)") (class "Default")
      (node (ref "PC4") (pin "A") (pinfunction "A_A") (pintype "passive"))
      (node (ref "R11") (pin "2") (pinfunction "2_2") (pintype "passive"))
    )
    (net (code "217") (name "Net-(PC4-PadB)") (class "Default")
      (node (ref "PC4") (pin "B") (pinfunction "B_B") (pintype "passive"))
      (node (ref "T11") (pin "C") (pinfunction "C_C") (pintype "passive"))
    )
    (net (code "218") (name "Net-(PC5-PadA)") (class "Default")
      (node (ref "PC5") (pin "A") (pinfunction "A_A") (pintype "passive"))
      (node (ref "R12") (pin "2") (pinfunction "2_2") (pintype "passive"))
    )
    (net (code "219") (name "Net-(PC5-PadB)") (class "Default")
      (node (ref "PC5") (pin "B") (pinfunction "B_B") (pintype "passive"))
      (node (ref "T12") (pin "C") (pinfunction "C_C") (pintype "passive"))
    )
    (net (code "220") (name "Net-(PC6-PadA)") (class "Default")
      (node (ref "PC6") (pin "A") (pinfunction "A_A") (pintype "passive"))
      (node (ref "R13") (pin "2") (pinfunction "2_2") (pintype "passive"))
    )
    (net (code "221") (name "Net-(PC6-PadB)") (class "Default")
      (node (ref "PC6") (pin "B") (pinfunction "B_B") (pintype "passive"))
      (node (ref "T13") (pin "C") (pinfunction "C_C") (pintype "passive"))
    )
    (net (code "222") (name "Net-(PC7-PadA)") (class "Default")
      (node (ref "PC7") (pin "A") (pinfunction "A_A") (pintype "passive"))
      (node (ref "R14") (pin "2") (pinfunction "2_2") (pintype "passive"))
    )
    (net (code "223") (name "Net-(PC7-PadB)") (class "Default")
      (node (ref "PC7") (pin "B") (pinfunction "B_B") (pintype "passive"))
      (node (ref "T14") (pin "C") (pinfunction "C_C") (pintype "passive"))
    )
    (net (code "224") (name "Net-(PC8-PadA)") (class "Default")
      (node (ref "PC8") (pin "A") (pinfunction "A_A") (pintype "passive"))
      (node (ref "R15") (pin "2") (pinfunction "2_2") (pintype "passive"))
    )
    (net (code "225") (name "Net-(PC8-PadB)") (class "Default")
      (node (ref "PC8") (pin "B") (pinfunction "B_B") (pintype "passive"))
      (node (ref "T15") (pin "C") (pinfunction "C_C") (pintype "passive"))
    )
    (net (code "226") (name "Net-(PC9-PadA)") (class "Default")
      (node (ref "PC9") (pin "A") (pinfunction "A_A") (pintype "passive"))
      (node (ref "R16") (pin "2") (pinfunction "2_2") (pintype "passive"))
    )
    (net (code "227") (name "Net-(PC9-PadB)") (class "Default")
      (node (ref "PC9") (pin "B") (pinfunction "B_B") (pintype "passive"))
      (node (ref "T16") (pin "C") (pinfunction "C_C") (pintype "passive"))
    )
    (net (code "228") (name "Net-(PC10-PadA)") (class "Default")
      (node (ref "PC10") (pin "A") (pinfunction "A_A") (pintype "passive"))
      (node (ref "R17") (pin "2") (pinfunction "2_2") (pintype "passive"))
    )
    (net (code "229") (name "Net-(PC10-PadB)") (class "Default")
      (node (ref "PC10") (pin "B") (pinfunction "B_B") (pintype "passive"))
      (node (ref "T17") (pin "C") (pinfunction "C_C") (pintype "passive"))
    )
    (net (code "230") (name "Net-(PC11-PadA)") (class "Default")
      (node (ref "PC11") (pin "A") (pinfunction "A_A") (pintype "passive"))
      (node (ref "R18") (pin "2") (pinfunction "2_2") (pintype "passive"))
    )
    (net (code "231") (name "Net-(PC11-PadB)") (class "Default")
      (node (ref "PC11") (pin "B") (pinfunction "B_B") (pintype "passive"))
      (node (ref "T18") (pin "C") (pinfunction "C_C") (pintype "passive"))
    )
    (net (code "232") (name "Net-(R67-Pad2)") (class "Default")
      (node (ref "R67") (pin "2") (pinfunction "2_2") (pintype "passive"))
      (node (ref "SC0") (pin "A") (pinfunction "A_A") (pintype "passive"))
    )
    (net (code "233") (name "Net-(R68-Pad2)") (class "Default")
      (node (ref "R68") (pin "2") (pinfunction "2_2") (pintype "passive"))
      (node (ref "SC1") (pin "A") (pinfunction "A_A") (pintype "passive"))
    )
    (net (code "234") (name "Net-(R69-Pad2)") (class "Default")
      (node (ref "R69") (pin "2") (pinfunction "2_2") (pintype "passive"))
      (node (ref "SC2") (pin "A") (pinfunction "A_A") (pintype "passive"))
    )
    (net (code "235") (name "Net-(R70-Pad2)") (class "Default")
      (node (ref "R70") (pin "2") (pinfunction "2_2") (pintype "passive"))
      (node (ref "SC3") (pin "A") (pinfunction "A_A") (pintype "passive"))
    )
    (net (code "236") (name "Net-(R71-Pad2)") (class "Default")
      (node (ref "R71") (pin "2") (pinfunction "2_2") (pintype "passive"))
      (node (ref "SC4") (pin "A") (pinfunction "A_A") (pintype "passive"))
    )
    (net (code "237") (name "Net-(R75-Pad2)") (class "Default")
      (node (ref "R75") (pin "2") (pinfunction "2_2") (pintype "passive"))
      (node (ref "RUN") (pin "A") (pinfunction "A_A") (pintype "passive"))
    )
    (net (code "238") (name "Net-(R79-Pad2)") (class "Default")
      (node (ref "R79") (pin "2") (pinfunction "2_2") (pintype "passive"))
      (node (ref "WORDCOUNT") (pin "A") (pinfunction "A_A") (pintype "passive"))
    )
    (net (code "239") (name "Net-(R83-Pad2)") (class "Default")
      (node (ref "R83") (pin "2") (pinfunction "2_2") (pintype "passive"))
      (node (ref "TAD") (pin "A") (pinfunction "A_A") (pintype "passive"))
    )
    (net (code "240") (name "Net-(RUN-PadB)") (class "Default")
      (node (ref "RUN") (pin "B") (pinfunction "B_B") (pintype "passive"))
      (node (ref "T75") (pin "C") (pinfunction "C_C") (pintype "passive"))
    )
    (net (code "241") (name "Net-(SC0-PadB)") (class "Default")
      (node (ref "SC0") (pin "B") (pinfunction "B_B") (pintype "passive"))
      (node (ref "T67") (pin "C") (pinfunction "C_C") (pintype "passive"))
    )
    (net (code "242") (name "Net-(SC1-PadB)") (class "Default")
      (node (ref "SC1") (pin "B") (pinfunction "B_B") (pintype "passive"))
      (node (ref "T68") (pin "C") (pinfunction "C_C") (pintype "passive"))
    )
    (net (code "243") (name "Net-(SC2-PadB)") (class "Default")
      (node (ref "SC2") (pin "B") (pinfunction "B_B") (pintype "passive"))
      (node (ref "T69") (pin "C") (pinfunction "C_C") (pintype "passive"))
    )
    (net (code "244") (name "Net-(SC3-PadB)") (class "Default")
      (node (ref "SC3") (pin "B") (pinfunction "B_B") (pintype "passive"))
      (node (ref "T70") (pin "C") (pinfunction "C_C") (pintype "passive"))
    )
    (net (code "245") (name "Net-(SC4-PadB)") (class "Default")
      (node (ref "SC4") (pin "B") (pinfunction "B_B") (pintype "passive"))
      (node (ref "T71") (pin "C") (pinfunction "C_C") (pintype "passive"))
    )
    (net (code "246") (name "Net-(T79-PadC)") (class "Default")
      (node (ref "T79") (pin "C") (pinfunction "C_C") (pintype "passive"))
      (node (ref "WORDCOUNT") (pin "B") (pinfunction "B_B") (pintype "passive"))
    )
    (net (code "247") (name "Net-(T83-PadC)") (class "Default")
      (node (ref "T83") (pin "C") (pinfunction "C_C") (pintype "passive"))
      (node (ref "TAD") (pin "B") (pinfunction "B_B") (pintype "passive"))
    )
    (net (code "248") (name "OPR") (class "Default")
      (node (ref "D40") (pin "16") (pinfunction "16_16") (pintype "passive"))
      (node (ref "F40BOT") (pin "11") (pinfunction "1_11") (pintype "passive"))
      (node (ref "T89") (pin "B") (pinfunction "B_B") (pintype "passive"))
    )
    (net (code "249") (name "PAUSE") (class "Default")
      (node (ref "D40") (pin "31") (pinfunction "31_31") (pintype "passive"))
      (node (ref "F40TOP") (pin "17") (pinfunction "1_17") (pintype "passive"))
      (node (ref "T74") (pin "B") (pinfunction "B_B") (pintype "passive"))
    )
    (net (code "250") (name "PC0") (class "Default")
      (node (ref "D40TOP") (pin "1") (pinfunction "1_1") (pintype "passive"))
      (node (ref "E40") (pin "1") (pinfunction "1_1") (pintype "passive"))
      (node (ref "T7") (pin "B") (pinfunction "B_B") (pintype "passive"))
    )
    (net (code "251") (name "PC1") (class "Default")
      (node (ref "D40BOT") (pin "5") (pinfunction "1_5") (pintype "passive"))
      (node (ref "E40") (pin "10") (pinfunction "10_10") (pintype "passive"))
      (node (ref "T8") (pin "B") (pinfunction "B_B") (pintype "passive"))
    )
    (net (code "252") (name "PC2") (class "Default")
      (node (ref "D40TOP") (pin "6") (pinfunction "1_6") (pintype "passive"))
      (node (ref "E40") (pin "11") (pinfunction "11_11") (pintype "passive"))
      (node (ref "T9") (pin "B") (pinfunction "B_B") (pintype "passive"))
    )
    (net (code "253") (name "PC3") (class "Default")
      (node (ref "D40BOT") (pin "14") (pinfunction "1_14") (pintype "passive"))
      (node (ref "E40") (pin "24") (pinfunction "24_24") (pintype "passive"))
      (node (ref "T10") (pin "B") (pinfunction "B_B") (pintype "passive"))
    )
    (net (code "254") (name "PC4") (class "Default")
      (node (ref "D40TOP") (pin "14") (pinfunction "1_14") (pintype "passive"))
      (node (ref "E40") (pin "25") (pinfunction "25_25") (pintype "passive"))
      (node (ref "T11") (pin "B") (pinfunction "B_B") (pintype "passive"))
    )
    (net (code "255") (name "PC5") (class "Default")
      (node (ref "D40BOT") (pin "19") (pinfunction "1_19") (pintype "passive"))
      (node (ref "E40") (pin "34") (pinfunction "34_34") (pintype "passive"))
      (node (ref "T12") (pin "B") (pinfunction "B_B") (pintype "passive"))
    )
    (net (code "256") (name "PC6") (class "Default")
      (node (ref "E40TOP") (pin "1") (pinfunction "1_1") (pintype "passive"))
      (node (ref "F40") (pin "1") (pinfunction "1_1") (pintype "passive"))
      (node (ref "T13") (pin "B") (pinfunction "B_B") (pintype "passive"))
    )
    (net (code "257") (name "PC7") (class "Default")
      (node (ref "E40BOT") (pin "5") (pinfunction "1_5") (pintype "passive"))
      (node (ref "F40") (pin "10") (pinfunction "10_10") (pintype "passive"))
      (node (ref "T14") (pin "B") (pinfunction "B_B") (pintype "passive"))
    )
    (net (code "258") (name "PC8") (class "Default")
      (node (ref "E40TOP") (pin "6") (pinfunction "1_6") (pintype "passive"))
      (node (ref "F40") (pin "11") (pinfunction "11_11") (pintype "passive"))
      (node (ref "T15") (pin "B") (pinfunction "B_B") (pintype "passive"))
    )
    (net (code "259") (name "PC9") (class "Default")
      (node (ref "E40BOT") (pin "14") (pinfunction "1_14") (pintype "passive"))
      (node (ref "F40") (pin "24") (pinfunction "24_24") (pintype "passive"))
      (node (ref "T16") (pin "B") (pinfunction "B_B") (pintype "passive"))
    )
    (net (code "260") (name "PC10") (class "Default")
      (node (ref "E40TOP") (pin "14") (pinfunction "1_14") (pintype "passive"))
      (node (ref "F40") (pin "25") (pinfunction "25_25") (pintype "passive"))
      (node (ref "T17") (pin "B") (pinfunction "B_B") (pintype "passive"))
    )
    (net (code "261") (name "PC11") (class "Default")
      (node (ref "E40BOT") (pin "19") (pinfunction "1_19") (pintype "passive"))
      (node (ref "F40") (pin "34") (pinfunction "34_34") (pintype "passive"))
      (node (ref "T18") (pin "B") (pinfunction "B_B") (pintype "passive"))
    )
    (net (code "262") (name "RUN") (class "Default")
      (node (ref "D40") (pin "33") (pinfunction "33_33") (pintype "passive"))
      (node (ref "F40TOP") (pin "18") (pinfunction "1_18") (pintype "passive"))
      (node (ref "T75") (pin "B") (pinfunction "B_B") (pintype "passive"))
    )
    (net (code "263") (name "SC0") (class "Default")
      (node (ref "C40") (pin "9") (pinfunction "9_9") (pintype "passive"))
      (node (ref "C40TOP") (pin "5") (pinfunction "1_5") (pintype "passive"))
      (node (ref "T67") (pin "B") (pinfunction "B_B") (pintype "passive"))
    )
    (net (code "264") (name "SC1") (class "Default")
      (node (ref "C40") (pin "2") (pinfunction "2_2") (pintype "passive"))
      (node (ref "C40BOT") (pin "1") (pinfunction "1_1") (pintype "passive"))
      (node (ref "T68") (pin "B") (pinfunction "B_B") (pintype "passive"))
    )
    (net (code "265") (name "SC2") (class "Default")
      (node (ref "C40") (pin "23") (pinfunction "23_23") (pintype "passive"))
      (node (ref "C40TOP") (pin "13") (pinfunction "1_13") (pintype "passive"))
      (node (ref "T69") (pin "B") (pinfunction "B_B") (pintype "passive"))
    )
    (net (code "266") (name "SC3") (class "Default")
      (node (ref "C40") (pin "12") (pinfunction "12_12") (pintype "passive"))
      (node (ref "C40BOT") (pin "6") (pinfunction "1_6") (pintype "passive"))
      (node (ref "T70") (pin "B") (pinfunction "B_B") (pintype "passive"))
    )
    (net (code "267") (name "SC4") (class "Default")
      (node (ref "C40") (pin "33") (pinfunction "33_33") (pintype "passive"))
      (node (ref "C40TOP") (pin "18") (pinfunction "1_18") (pintype "passive"))
      (node (ref "T71") (pin "B") (pinfunction "B_B") (pintype "passive"))
    )
    (net (code "268") (name "TAD") (class "Default")
      (node (ref "D40") (pin "4") (pinfunction "4_4") (pintype "passive"))
      (node (ref "F40BOT") (pin "2") (pinfunction "1_2") (pintype "passive"))
      (node (ref "T83") (pin "B") (pinfunction "B_B") (pintype "passive"))
    )
    (net (code "269") (name "WC") (class "Default")
      (node (ref "D40") (pin "30") (pinfunction "30_30") (pintype "passive"))
      (node (ref "F40BOT") (pin "17") (pinfunction "1_17") (pintype "passive"))
      (node (ref "T79") (pin "B") (pinfunction "B_B") (pintype "passive"))
    )
    (net (code "270") (name "unconnected-(C40-Pad3)") (class "Default")
      (node (ref "C40") (pin "3") (pinfunction "3_3") (pintype "passive"))
    )
    (net (code "271") (name "unconnected-(C40-Pad4)") (class "Default")
      (node (ref "C40") (pin "4") (pinfunction "4_4") (pintype "passive"))
    )
    (net (code "272") (name "unconnected-(C40-Pad5)") (class "Default")
      (node (ref "C40") (pin "5") (pinfunction "5_5") (pintype "passive"))
    )
    (net (code "273") (name "unconnected-(C40-Pad6)") (class "Default")
      (node (ref "C40") (pin "6") (pinfunction "6_6") (pintype "passive"))
    )
    (net (code "274") (name "unconnected-(C40-Pad7)") (class "Default")
      (node (ref "C40") (pin "7") (pinfunction "7_7") (pintype "passive"))
    )
    (net (code "275") (name "unconnected-(C40-Pad8)") (class "Default")
      (node (ref "C40") (pin "8") (pinfunction "8_8") (pintype "passive"))
    )
    (net (code "276") (name "unconnected-(C40-Pad13)") (class "Default")
      (node (ref "C40") (pin "13") (pinfunction "13_13") (pintype "passive"))
    )
    (net (code "277") (name "unconnected-(C40-Pad14)") (class "Default")
      (node (ref "C40") (pin "14") (pinfunction "14_14") (pintype "passive"))
    )
    (net (code "278") (name "unconnected-(C40-Pad15)") (class "Default")
      (node (ref "C40") (pin "15") (pinfunction "15_15") (pintype "passive"))
    )
    (net (code "279") (name "unconnected-(C40-Pad16)") (class "Default")
      (node (ref "C40") (pin "16") (pinfunction "16_16") (pintype "passive"))
    )
    (net (code "280") (name "unconnected-(C40-Pad21)") (class "Default")
      (node (ref "C40") (pin "21") (pinfunction "21_21") (pintype "passive"))
    )
    (net (code "281") (name "unconnected-(C40-Pad22)") (class "Default")
      (node (ref "C40") (pin "22") (pinfunction "22_22") (pintype "passive"))
    )
    (net (code "282") (name "unconnected-(C40-Pad26)") (class "Default")
      (node (ref "C40") (pin "26") (pinfunction "26_26") (pintype "passive"))
    )
    (net (code "283") (name "unconnected-(C40-Pad27)") (class "Default")
      (node (ref "C40") (pin "27") (pinfunction "27_27") (pintype "passive"))
    )
    (net (code "284") (name "unconnected-(C40-Pad29)") (class "Default")
      (node (ref "C40") (pin "29") (pinfunction "29_29") (pintype "passive"))
    )
    (net (code "285") (name "unconnected-(C40-Pad30)") (class "Default")
      (node (ref "C40") (pin "30") (pinfunction "30_30") (pintype "passive"))
    )
    (net (code "286") (name "unconnected-(C40-Pad31)") (class "Default")
      (node (ref "C40") (pin "31") (pinfunction "31_31") (pintype "passive"))
    )
    (net (code "287") (name "unconnected-(C40-Pad32)") (class "Default")
      (node (ref "C40") (pin "32") (pinfunction "32_32") (pintype "passive"))
    )
    (net (code "288") (name "unconnected-(D40-Pad1)") (class "Default")
      (node (ref "D40") (pin "1") (pinfunction "1_1") (pintype "passive"))
    )
    (net (code "289") (name "unconnected-(D40-Pad3)") (class "Default")
      (node (ref "D40") (pin "3") (pinfunction "3_3") (pintype "passive"))
    )
    (net (code "290") (name "unconnected-(D40-Pad5)") (class "Default")
      (node (ref "D40") (pin "5") (pinfunction "5_5") (pintype "passive"))
    )
    (net (code "291") (name "unconnected-(D40-Pad7)") (class "Default")
      (node (ref "D40") (pin "7") (pinfunction "7_7") (pintype "passive"))
    )
    (net (code "292") (name "unconnected-(D40-Pad9)") (class "Default")
      (node (ref "D40") (pin "9") (pinfunction "9_9") (pintype "passive"))
    )
    (net (code "293") (name "unconnected-(D40-Pad11)") (class "Default")
      (node (ref "D40") (pin "11") (pinfunction "11_11") (pintype "passive"))
    )
    (net (code "294") (name "unconnected-(D40-Pad13)") (class "Default")
      (node (ref "D40") (pin "13") (pinfunction "13_13") (pintype "passive"))
    )
    (net (code "295") (name "unconnected-(D40-Pad14)") (class "Default")
      (node (ref "D40") (pin "14") (pinfunction "14_14") (pintype "passive"))
    )
    (net (code "296") (name "unconnected-(D40-Pad15)") (class "Default")
      (node (ref "D40") (pin "15") (pinfunction "15_15") (pintype "passive"))
    )
    (net (code "297") (name "unconnected-(D40-Pad21)") (class "Default")
      (node (ref "D40") (pin "21") (pinfunction "21_21") (pintype "passive"))
    )
    (net (code "298") (name "unconnected-(D40-Pad25)") (class "Default")
      (node (ref "D40") (pin "25") (pinfunction "25_25") (pintype "passive"))
    )
    (net (code "299") (name "unconnected-(D40-Pad27)") (class "Default")
      (node (ref "D40") (pin "27") (pinfunction "27_27") (pintype "passive"))
    )
    (net (code "300") (name "unconnected-(D40-Pad29)") (class "Default")
      (node (ref "D40") (pin "29") (pinfunction "29_29") (pintype "passive"))
    )
    (net (code "301") (name "unconnected-(U$10A-1-PadAA1)") (class "Default")
      (node (ref "U$10") (pin "AA1") (pinfunction "1_AA1") (pintype "bidirectional"))
    )
    (net (code "302") (name "unconnected-(U$10AA-1-PadAR1)") (class "Default")
      (node (ref "U$10") (pin "AR1") (pinfunction "1_AR1") (pintype "bidirectional"))
    )
    (net (code "303") (name "unconnected-(U$10AB-1-PadAR2)") (class "Default")
      (node (ref "U$10") (pin "AR2") (pinfunction "1_AR2") (pintype "bidirectional"))
    )
    (net (code "304") (name "unconnected-(U$10AC-1-PadAS1)") (class "Default")
      (node (ref "U$10") (pin "AS1") (pinfunction "1_AS1") (pintype "bidirectional"))
    )
    (net (code "305") (name "unconnected-(U$10AD-1-PadAS2)") (class "Default")
      (node (ref "U$10") (pin "AS2") (pinfunction "1_AS2") (pintype "bidirectional"))
    )
    (net (code "306") (name "unconnected-(U$10AE-1-PadAT1)") (class "Default")
      (node (ref "U$10") (pin "AT1") (pinfunction "1_AT1") (pintype "bidirectional"))
    )
    (net (code "307") (name "unconnected-(U$10AF-1-PadAT2)") (class "Default")
      (node (ref "U$10") (pin "AT2") (pinfunction "1_AT2") (pintype "bidirectional"))
    )
    (net (code "308") (name "unconnected-(U$10AG-1-PadAU1)") (class "Default")
      (node (ref "U$10") (pin "AU1") (pinfunction "1_AU1") (pintype "bidirectional"))
    )
    (net (code "309") (name "unconnected-(U$10AH-1-PadAU2)") (class "Default")
      (node (ref "U$10") (pin "AU2") (pinfunction "1_AU2") (pintype "bidirectional"))
    )
    (net (code "310") (name "unconnected-(U$10AI-1-PadAV1)") (class "Default")
      (node (ref "U$10") (pin "AV1") (pinfunction "1_AV1") (pintype "bidirectional"))
    )
    (net (code "311") (name "unconnected-(U$10AJ-1-PadAV2)") (class "Default")
      (node (ref "U$10") (pin "AV2") (pinfunction "1_AV2") (pintype "bidirectional"))
    )
    (net (code "312") (name "unconnected-(U$10AK-1-PadBA1)") (class "Default")
      (node (ref "U$10") (pin "BA1") (pinfunction "1_BA1") (pintype "bidirectional"))
    )
    (net (code "313") (name "unconnected-(U$10AL-1-PadBA2)") (class "Default")
      (node (ref "U$10") (pin "BA2") (pinfunction "1_BA2") (pintype "bidirectional"))
    )
    (net (code "314") (name "unconnected-(U$10AM-1-PadBB1)") (class "Default")
      (node (ref "U$10") (pin "BB1") (pinfunction "1_BB1") (pintype "bidirectional"))
    )
    (net (code "315") (name "unconnected-(U$10AN-1-PadBB2)") (class "Default")
      (node (ref "U$10") (pin "BB2") (pinfunction "1_BB2") (pintype "bidirectional"))
    )
    (net (code "316") (name "unconnected-(U$10AO-1-PadBC1)") (class "Default")
      (node (ref "U$10") (pin "BC1") (pinfunction "1_BC1") (pintype "bidirectional"))
    )
    (net (code "317") (name "unconnected-(U$10AP-1-PadBC2)") (class "Default")
      (node (ref "U$10") (pin "BC2") (pinfunction "1_BC2") (pintype "bidirectional"))
    )
    (net (code "318") (name "unconnected-(U$10AQ-1-PadBD1)") (class "Default")
      (node (ref "U$10") (pin "BD1") (pinfunction "1_BD1") (pintype "bidirectional"))
    )
    (net (code "319") (name "unconnected-(U$10AR-1-PadBD2)") (class "Default")
      (node (ref "U$10") (pin "BD2") (pinfunction "1_BD2") (pintype "bidirectional"))
    )
    (net (code "320") (name "unconnected-(U$10AS-1-PadBE1)") (class "Default")
      (node (ref "U$10") (pin "BE1") (pinfunction "1_BE1") (pintype "bidirectional"))
    )
    (net (code "321") (name "unconnected-(U$10AT-1-PadBE2)") (class "Default")
      (node (ref "U$10") (pin "BE2") (pinfunction "1_BE2") (pintype "bidirectional"))
    )
    (net (code "322") (name "unconnected-(U$10AU-1-PadBF1)") (class "Default")
      (node (ref "U$10") (pin "BF1") (pinfunction "1_BF1") (pintype "bidirectional"))
    )
    (net (code "323") (name "unconnected-(U$10AV-1-PadBF2)") (class "Default")
      (node (ref "U$10") (pin "BF2") (pinfunction "1_BF2") (pintype "bidirectional"))
    )
    (net (code "324") (name "unconnected-(U$10AW-1-PadBH1)") (class "Default")
      (node (ref "U$10") (pin "BH1") (pinfunction "1_BH1") (pintype "bidirectional"))
    )
    (net (code "325") (name "unconnected-(U$10AX-1-PadBH2)") (class "Default")
      (node (ref "U$10") (pin "BH2") (pinfunction "1_BH2") (pintype "bidirectional"))
    )
    (net (code "326") (name "unconnected-(U$10AY-1-PadBJ1)") (class "Default")
      (node (ref "U$10") (pin "BJ1") (pinfunction "1_BJ1") (pintype "bidirectional"))
    )
    (net (code "327") (name "unconnected-(U$10AZ-1-PadBJ2)") (class "Default")
      (node (ref "U$10") (pin "BJ2") (pinfunction "1_BJ2") (pintype "bidirectional"))
    )
    (net (code "328") (name "unconnected-(U$10B-1-PadAA2)") (class "Default")
      (node (ref "U$10") (pin "AA2") (pinfunction "1_AA2") (pintype "bidirectional"))
    )
    (net (code "329") (name "unconnected-(U$10BA-1-PadBK1)") (class "Default")
      (node (ref "U$10") (pin "BK1") (pinfunction "1_BK1") (pintype "bidirectional"))
    )
    (net (code "330") (name "unconnected-(U$10BB-1-PadBK2)") (class "Default")
      (node (ref "U$10") (pin "BK2") (pinfunction "1_BK2") (pintype "bidirectional"))
    )
    (net (code "331") (name "unconnected-(U$10BC-1-PadBL1)") (class "Default")
      (node (ref "U$10") (pin "BL1") (pinfunction "1_BL1") (pintype "bidirectional"))
    )
    (net (code "332") (name "unconnected-(U$10BD-1-PadBL2)") (class "Default")
      (node (ref "U$10") (pin "BL2") (pinfunction "1_BL2") (pintype "bidirectional"))
    )
    (net (code "333") (name "unconnected-(U$10BE-1-PadBM1)") (class "Default")
      (node (ref "U$10") (pin "BM1") (pinfunction "1_BM1") (pintype "bidirectional"))
    )
    (net (code "334") (name "unconnected-(U$10BF-1-PadBM2)") (class "Default")
      (node (ref "U$10") (pin "BM2") (pinfunction "1_BM2") (pintype "bidirectional"))
    )
    (net (code "335") (name "unconnected-(U$10BG-1-PadBN1)") (class "Default")
      (node (ref "U$10") (pin "BN1") (pinfunction "1_BN1") (pintype "bidirectional"))
    )
    (net (code "336") (name "unconnected-(U$10BH-1-PadBN2)") (class "Default")
      (node (ref "U$10") (pin "BN2") (pinfunction "1_BN2") (pintype "bidirectional"))
    )
    (net (code "337") (name "unconnected-(U$10BI-1-PadBP1)") (class "Default")
      (node (ref "U$10") (pin "BP1") (pinfunction "1_BP1") (pintype "bidirectional"))
    )
    (net (code "338") (name "unconnected-(U$10BJ-1-PadBP2)") (class "Default")
      (node (ref "U$10") (pin "BP2") (pinfunction "1_BP2") (pintype "bidirectional"))
    )
    (net (code "339") (name "unconnected-(U$10BK-1-PadBR1)") (class "Default")
      (node (ref "U$10") (pin "BR1") (pinfunction "1_BR1") (pintype "bidirectional"))
    )
    (net (code "340") (name "unconnected-(U$10BL-1-PadBR2)") (class "Default")
      (node (ref "U$10") (pin "BR2") (pinfunction "1_BR2") (pintype "bidirectional"))
    )
    (net (code "341") (name "unconnected-(U$10BM-1-PadBS1)") (class "Default")
      (node (ref "U$10") (pin "BS1") (pinfunction "1_BS1") (pintype "bidirectional"))
    )
    (net (code "342") (name "unconnected-(U$10BN-1-PadBS2)") (class "Default")
      (node (ref "U$10") (pin "BS2") (pinfunction "1_BS2") (pintype "bidirectional"))
    )
    (net (code "343") (name "unconnected-(U$10BO-1-PadBT1)") (class "Default")
      (node (ref "U$10") (pin "BT1") (pinfunction "1_BT1") (pintype "bidirectional"))
    )
    (net (code "344") (name "unconnected-(U$10BP-1-PadBT2)") (class "Default")
      (node (ref "U$10") (pin "BT2") (pinfunction "1_BT2") (pintype "bidirectional"))
    )
    (net (code "345") (name "unconnected-(U$10BQ-1-PadBU1)") (class "Default")
      (node (ref "U$10") (pin "BU1") (pinfunction "1_BU1") (pintype "bidirectional"))
    )
    (net (code "346") (name "unconnected-(U$10BR-1-PadBU2)") (class "Default")
      (node (ref "U$10") (pin "BU2") (pinfunction "1_BU2") (pintype "bidirectional"))
    )
    (net (code "347") (name "unconnected-(U$10BS-1-PadBV1)") (class "Default")
      (node (ref "U$10") (pin "BV1") (pinfunction "1_BV1") (pintype "bidirectional"))
    )
    (net (code "348") (name "unconnected-(U$10BT-1-PadBV2)") (class "Default")
      (node (ref "U$10") (pin "BV2") (pinfunction "1_BV2") (pintype "bidirectional"))
    )
    (net (code "349") (name "unconnected-(U$10BU-1-PadCA1)") (class "Default")
      (node (ref "U$10") (pin "CA1") (pinfunction "1_CA1") (pintype "bidirectional"))
    )
    (net (code "350") (name "unconnected-(U$10BV-1-PadCA2)") (class "Default")
      (node (ref "U$10") (pin "CA2") (pinfunction "1_CA2") (pintype "bidirectional"))
    )
    (net (code "351") (name "unconnected-(U$10BW-1-PadCB1)") (class "Default")
      (node (ref "U$10") (pin "CB1") (pinfunction "1_CB1") (pintype "bidirectional"))
    )
    (net (code "352") (name "unconnected-(U$10BX-1-PadCB2)") (class "Default")
      (node (ref "U$10") (pin "CB2") (pinfunction "1_CB2") (pintype "bidirectional"))
    )
    (net (code "353") (name "unconnected-(U$10BY-1-PadCC1)") (class "Default")
      (node (ref "U$10") (pin "CC1") (pinfunction "1_CC1") (pintype "bidirectional"))
    )
    (net (code "354") (name "unconnected-(U$10BZ-1-PadCC2)") (class "Default")
      (node (ref "U$10") (pin "CC2") (pinfunction "1_CC2") (pintype "bidirectional"))
    )
    (net (code "355") (name "unconnected-(U$10C-1-PadAB1)") (class "Default")
      (node (ref "U$10") (pin "AB1") (pinfunction "1_AB1") (pintype "bidirectional"))
    )
    (net (code "356") (name "unconnected-(U$10CA-1-PadCD1)") (class "Default")
      (node (ref "U$10") (pin "CD1") (pinfunction "1_CD1") (pintype "bidirectional"))
    )
    (net (code "357") (name "unconnected-(U$10CB-1-PadCD2)") (class "Default")
      (node (ref "U$10") (pin "CD2") (pinfunction "1_CD2") (pintype "bidirectional"))
    )
    (net (code "358") (name "unconnected-(U$10CC-1-PadCE1)") (class "Default")
      (node (ref "U$10") (pin "CE1") (pinfunction "1_CE1") (pintype "bidirectional"))
    )
    (net (code "359") (name "unconnected-(U$10CD-1-PadCE2)") (class "Default")
      (node (ref "U$10") (pin "CE2") (pinfunction "1_CE2") (pintype "bidirectional"))
    )
    (net (code "360") (name "unconnected-(U$10CE-1-PadCF1)") (class "Default")
      (node (ref "U$10") (pin "CF1") (pinfunction "1_CF1") (pintype "bidirectional"))
    )
    (net (code "361") (name "unconnected-(U$10CF-1-PadCF2)") (class "Default")
      (node (ref "U$10") (pin "CF2") (pinfunction "1_CF2") (pintype "bidirectional"))
    )
    (net (code "362") (name "unconnected-(U$10CG-1-PadCH1)") (class "Default")
      (node (ref "U$10") (pin "CH1") (pinfunction "1_CH1") (pintype "bidirectional"))
    )
    (net (code "363") (name "unconnected-(U$10CH-1-PadCH2)") (class "Default")
      (node (ref "U$10") (pin "CH2") (pinfunction "1_CH2") (pintype "bidirectional"))
    )
    (net (code "364") (name "unconnected-(U$10CI-1-PadCJ1)") (class "Default")
      (node (ref "U$10") (pin "CJ1") (pinfunction "1_CJ1") (pintype "bidirectional"))
    )
    (net (code "365") (name "unconnected-(U$10CJ-1-PadCJ2)") (class "Default")
      (node (ref "U$10") (pin "CJ2") (pinfunction "1_CJ2") (pintype "bidirectional"))
    )
    (net (code "366") (name "unconnected-(U$10CK-1-PadCK1)") (class "Default")
      (node (ref "U$10") (pin "CK1") (pinfunction "1_CK1") (pintype "bidirectional"))
    )
    (net (code "367") (name "unconnected-(U$10CL-1-PadCK2)") (class "Default")
      (node (ref "U$10") (pin "CK2") (pinfunction "1_CK2") (pintype "bidirectional"))
    )
    (net (code "368") (name "unconnected-(U$10CM-1-PadCL1)") (class "Default")
      (node (ref "U$10") (pin "CL1") (pinfunction "1_CL1") (pintype "bidirectional"))
    )
    (net (code "369") (name "unconnected-(U$10CN-1-PadCL2)") (class "Default")
      (node (ref "U$10") (pin "CL2") (pinfunction "1_CL2") (pintype "bidirectional"))
    )
    (net (code "370") (name "unconnected-(U$10CO-1-PadCM1)") (class "Default")
      (node (ref "U$10") (pin "CM1") (pinfunction "1_CM1") (pintype "bidirectional"))
    )
    (net (code "371") (name "unconnected-(U$10CP-1-PadCM2)") (class "Default")
      (node (ref "U$10") (pin "CM2") (pinfunction "1_CM2") (pintype "bidirectional"))
    )
    (net (code "372") (name "unconnected-(U$10CQ-1-PadCN1)") (class "Default")
      (node (ref "U$10") (pin "CN1") (pinfunction "1_CN1") (pintype "bidirectional"))
    )
    (net (code "373") (name "unconnected-(U$10CR-1-PadCN2)") (class "Default")
      (node (ref "U$10") (pin "CN2") (pinfunction "1_CN2") (pintype "bidirectional"))
    )
    (net (code "374") (name "unconnected-(U$10CS-1-PadCP1)") (class "Default")
      (node (ref "U$10") (pin "CP1") (pinfunction "1_CP1") (pintype "bidirectional"))
    )
    (net (code "375") (name "unconnected-(U$10CT-1-PadCP2)") (class "Default")
      (node (ref "U$10") (pin "CP2") (pinfunction "1_CP2") (pintype "bidirectional"))
    )
    (net (code "376") (name "unconnected-(U$10CU-1-PadCR1)") (class "Default")
      (node (ref "U$10") (pin "CR1") (pinfunction "1_CR1") (pintype "bidirectional"))
    )
    (net (code "377") (name "unconnected-(U$10CV-1-PadCR2)") (class "Default")
      (node (ref "U$10") (pin "CR2") (pinfunction "1_CR2") (pintype "bidirectional"))
    )
    (net (code "378") (name "unconnected-(U$10CW-1-PadCS1)") (class "Default")
      (node (ref "U$10") (pin "CS1") (pinfunction "1_CS1") (pintype "bidirectional"))
    )
    (net (code "379") (name "unconnected-(U$10CX-1-PadCS2)") (class "Default")
      (node (ref "U$10") (pin "CS2") (pinfunction "1_CS2") (pintype "bidirectional"))
    )
    (net (code "380") (name "unconnected-(U$10CY-1-PadCT1)") (class "Default")
      (node (ref "U$10") (pin "CT1") (pinfunction "1_CT1") (pintype "bidirectional"))
    )
    (net (code "381") (name "unconnected-(U$10CZ-1-PadCT2)") (class "Default")
      (node (ref "U$10") (pin "CT2") (pinfunction "1_CT2") (pintype "bidirectional"))
    )
    (net (code "382") (name "unconnected-(U$10D-1-PadAB2)") (class "Default")
      (node (ref "U$10") (pin "AB2") (pinfunction "1_AB2") (pintype "bidirectional"))
    )
    (net (code "383") (name "unconnected-(U$10DA-1-PadCU1)") (class "Default")
      (node (ref "U$10") (pin "CU1") (pinfunction "1_CU1") (pintype "bidirectional"))
    )
    (net (code "384") (name "unconnected-(U$10DB-1-PadCU2)") (class "Default")
      (node (ref "U$10") (pin "CU2") (pinfunction "1_CU2") (pintype "bidirectional"))
    )
    (net (code "385") (name "unconnected-(U$10DC-1-PadCV1)") (class "Default")
      (node (ref "U$10") (pin "CV1") (pinfunction "1_CV1") (pintype "bidirectional"))
    )
    (net (code "386") (name "unconnected-(U$10DD-1-PadCV2)") (class "Default")
      (node (ref "U$10") (pin "CV2") (pinfunction "1_CV2") (pintype "bidirectional"))
    )
    (net (code "387") (name "unconnected-(U$10DE-1-PadDA1)") (class "Default")
      (node (ref "U$10") (pin "DA1") (pinfunction "1_DA1") (pintype "bidirectional"))
    )
    (net (code "388") (name "unconnected-(U$10DF-1-PadDA2)") (class "Default")
      (node (ref "U$10") (pin "DA2") (pinfunction "1_DA2") (pintype "bidirectional"))
    )
    (net (code "389") (name "unconnected-(U$10DG-1-PadDB1)") (class "Default")
      (node (ref "U$10") (pin "DB1") (pinfunction "1_DB1") (pintype "bidirectional"))
    )
    (net (code "390") (name "unconnected-(U$10DH-1-PadDB2)") (class "Default")
      (node (ref "U$10") (pin "DB2") (pinfunction "1_DB2") (pintype "bidirectional"))
    )
    (net (code "391") (name "unconnected-(U$10DI-1-PadDC1)") (class "Default")
      (node (ref "U$10") (pin "DC1") (pinfunction "1_DC1") (pintype "bidirectional"))
    )
    (net (code "392") (name "unconnected-(U$10DJ-1-PadDC2)") (class "Default")
      (node (ref "U$10") (pin "DC2") (pinfunction "1_DC2") (pintype "bidirectional"))
    )
    (net (code "393") (name "unconnected-(U$10DK-1-PadDD1)") (class "Default")
      (node (ref "U$10") (pin "DD1") (pinfunction "1_DD1") (pintype "bidirectional"))
    )
    (net (code "394") (name "unconnected-(U$10DL-1-PadDD2)") (class "Default")
      (node (ref "U$10") (pin "DD2") (pinfunction "1_DD2") (pintype "bidirectional"))
    )
    (net (code "395") (name "unconnected-(U$10DM-1-PadDE1)") (class "Default")
      (node (ref "U$10") (pin "DE1") (pinfunction "1_DE1") (pintype "bidirectional"))
    )
    (net (code "396") (name "unconnected-(U$10DN-1-PadDE2)") (class "Default")
      (node (ref "U$10") (pin "DE2") (pinfunction "1_DE2") (pintype "bidirectional"))
    )
    (net (code "397") (name "unconnected-(U$10DO-1-PadDF1)") (class "Default")
      (node (ref "U$10") (pin "DF1") (pinfunction "1_DF1") (pintype "bidirectional"))
    )
    (net (code "398") (name "unconnected-(U$10DP-1-PadDF2)") (class "Default")
      (node (ref "U$10") (pin "DF2") (pinfunction "1_DF2") (pintype "bidirectional"))
    )
    (net (code "399") (name "unconnected-(U$10DQ-1-PadDH1)") (class "Default")
      (node (ref "U$10") (pin "DH1") (pinfunction "1_DH1") (pintype "bidirectional"))
    )
    (net (code "400") (name "unconnected-(U$10DR-1-PadDH2)") (class "Default")
      (node (ref "U$10") (pin "DH2") (pinfunction "1_DH2") (pintype "bidirectional"))
    )
    (net (code "401") (name "unconnected-(U$10DS-1-PadDJ1)") (class "Default")
      (node (ref "U$10") (pin "DJ1") (pinfunction "1_DJ1") (pintype "bidirectional"))
    )
    (net (code "402") (name "unconnected-(U$10DT-1-PadDJ2)") (class "Default")
      (node (ref "U$10") (pin "DJ2") (pinfunction "1_DJ2") (pintype "bidirectional"))
    )
    (net (code "403") (name "unconnected-(U$10DU-1-PadDK1)") (class "Default")
      (node (ref "U$10") (pin "DK1") (pinfunction "1_DK1") (pintype "bidirectional"))
    )
    (net (code "404") (name "unconnected-(U$10DV-1-PadDK2)") (class "Default")
      (node (ref "U$10") (pin "DK2") (pinfunction "1_DK2") (pintype "bidirectional"))
    )
    (net (code "405") (name "unconnected-(U$10DW-1-PadDL1)") (class "Default")
      (node (ref "U$10") (pin "DL1") (pinfunction "1_DL1") (pintype "bidirectional"))
    )
    (net (code "406") (name "unconnected-(U$10DX-1-PadDL2)") (class "Default")
      (node (ref "U$10") (pin "DL2") (pinfunction "1_DL2") (pintype "bidirectional"))
    )
    (net (code "407") (name "unconnected-(U$10DY-1-PadDM1)") (class "Default")
      (node (ref "U$10") (pin "DM1") (pinfunction "1_DM1") (pintype "bidirectional"))
    )
    (net (code "408") (name "unconnected-(U$10DZ-1-PadDM2)") (class "Default")
      (node (ref "U$10") (pin "DM2") (pinfunction "1_DM2") (pintype "bidirectional"))
    )
    (net (code "409") (name "unconnected-(U$10E-1-PadAC1)") (class "Default")
      (node (ref "U$10") (pin "AC1") (pinfunction "1_AC1") (pintype "bidirectional"))
    )
    (net (code "410") (name "unconnected-(U$10EA-1-PadDN1)") (class "Default")
      (node (ref "U$10") (pin "DN1") (pinfunction "1_DN1") (pintype "bidirectional"))
    )
    (net (code "411") (name "unconnected-(U$10EB-1-PadDN2)") (class "Default")
      (node (ref "U$10") (pin "DN2") (pinfunction "1_DN2") (pintype "bidirectional"))
    )
    (net (code "412") (name "unconnected-(U$10EC-1-PadDP1)") (class "Default")
      (node (ref "U$10") (pin "DP1") (pinfunction "1_DP1") (pintype "bidirectional"))
    )
    (net (code "413") (name "unconnected-(U$10ED-1-PadDP2)") (class "Default")
      (node (ref "U$10") (pin "DP2") (pinfunction "1_DP2") (pintype "bidirectional"))
    )
    (net (code "414") (name "unconnected-(U$10EE-1-PadDR1)") (class "Default")
      (node (ref "U$10") (pin "DR1") (pinfunction "1_DR1") (pintype "bidirectional"))
    )
    (net (code "415") (name "unconnected-(U$10EF-1-PadDR2)") (class "Default")
      (node (ref "U$10") (pin "DR2") (pinfunction "1_DR2") (pintype "bidirectional"))
    )
    (net (code "416") (name "unconnected-(U$10EG-1-PadDS1)") (class "Default")
      (node (ref "U$10") (pin "DS1") (pinfunction "1_DS1") (pintype "bidirectional"))
    )
    (net (code "417") (name "unconnected-(U$10EH-1-PadDS2)") (class "Default")
      (node (ref "U$10") (pin "DS2") (pinfunction "1_DS2") (pintype "bidirectional"))
    )
    (net (code "418") (name "unconnected-(U$10EI-1-PadDT1)") (class "Default")
      (node (ref "U$10") (pin "DT1") (pinfunction "1_DT1") (pintype "bidirectional"))
    )
    (net (code "419") (name "unconnected-(U$10EJ-1-PadDT2)") (class "Default")
      (node (ref "U$10") (pin "DT2") (pinfunction "1_DT2") (pintype "bidirectional"))
    )
    (net (code "420") (name "unconnected-(U$10EK-1-PadDU1)") (class "Default")
      (node (ref "U$10") (pin "DU1") (pinfunction "1_DU1") (pintype "bidirectional"))
    )
    (net (code "421") (name "unconnected-(U$10EL-1-PadDU2)") (class "Default")
      (node (ref "U$10") (pin "DU2") (pinfunction "1_DU2") (pintype "bidirectional"))
    )
    (net (code "422") (name "unconnected-(U$10EM-1-PadDV1)") (class "Default")
      (node (ref "U$10") (pin "DV1") (pinfunction "1_DV1") (pintype "bidirectional"))
    )
    (net (code "423") (name "unconnected-(U$10EN-1-PadDV2)") (class "Default")
      (node (ref "U$10") (pin "DV2") (pinfunction "1_DV2") (pintype "bidirectional"))
    )
    (net (code "424") (name "unconnected-(U$10F-1-PadAC2)") (class "Default")
      (node (ref "U$10") (pin "AC2") (pinfunction "1_AC2") (pintype "bidirectional"))
    )
    (net (code "425") (name "unconnected-(U$10G-1-PadAD1)") (class "Default")
      (node (ref "U$10") (pin "AD1") (pinfunction "1_AD1") (pintype "bidirectional"))
    )
    (net (code "426") (name "unconnected-(U$10H-1-PadAD2)") (class "Default")
      (node (ref "U$10") (pin "AD2") (pinfunction "1_AD2") (pintype "bidirectional"))
    )
    (net (code "427") (name "unconnected-(U$10I-1-PadAE1)") (class "Default")
      (node (ref "U$10") (pin "AE1") (pinfunction "1_AE1") (pintype "bidirectional"))
    )
    (net (code "428") (name "unconnected-(U$10J-1-PadAE2)") (class "Default")
      (node (ref "U$10") (pin "AE2") (pinfunction "1_AE2") (pintype "bidirectional"))
    )
    (net (code "429") (name "unconnected-(U$10K-1-PadAF1)") (class "Default")
      (node (ref "U$10") (pin "AF1") (pinfunction "1_AF1") (pintype "bidirectional"))
    )
    (net (code "430") (name "unconnected-(U$10L-1-PadAF2)") (class "Default")
      (node (ref "U$10") (pin "AF2") (pinfunction "1_AF2") (pintype "bidirectional"))
    )
    (net (code "431") (name "unconnected-(U$10M-1-PadAH1)") (class "Default")
      (node (ref "U$10") (pin "AH1") (pinfunction "1_AH1") (pintype "bidirectional"))
    )
    (net (code "432") (name "unconnected-(U$10N-1-PadAH2)") (class "Default")
      (node (ref "U$10") (pin "AH2") (pinfunction "1_AH2") (pintype "bidirectional"))
    )
    (net (code "433") (name "unconnected-(U$10O-1-PadAJ1)") (class "Default")
      (node (ref "U$10") (pin "AJ1") (pinfunction "1_AJ1") (pintype "bidirectional"))
    )
    (net (code "434") (name "unconnected-(U$10P-1-PadAJ2)") (class "Default")
      (node (ref "U$10") (pin "AJ2") (pinfunction "1_AJ2") (pintype "bidirectional"))
    )
    (net (code "435") (name "unconnected-(U$10Q-1-PadAK1)") (class "Default")
      (node (ref "U$10") (pin "AK1") (pinfunction "1_AK1") (pintype "bidirectional"))
    )
    (net (code "436") (name "unconnected-(U$10R-1-PadAK2)") (class "Default")
      (node (ref "U$10") (pin "AK2") (pinfunction "1_AK2") (pintype "bidirectional"))
    )
    (net (code "437") (name "unconnected-(U$10S-1-PadAL1)") (class "Default")
      (node (ref "U$10") (pin "AL1") (pinfunction "1_AL1") (pintype "bidirectional"))
    )
    (net (code "438") (name "unconnected-(U$10T-1-PadAL2)") (class "Default")
      (node (ref "U$10") (pin "AL2") (pinfunction "1_AL2") (pintype "bidirectional"))
    )
    (net (code "439") (name "unconnected-(U$10U-1-PadAM1)") (class "Default")
      (node (ref "U$10") (pin "AM1") (pinfunction "1_AM1") (pintype "bidirectional"))
    )
    (net (code "440") (name "unconnected-(U$10V-1-PadAM2)") (class "Default")
      (node (ref "U$10") (pin "AM2") (pinfunction "1_AM2") (pintype "bidirectional"))
    )
    (net (code "441") (name "unconnected-(U$10W-1-PadAN1)") (class "Default")
      (node (ref "U$10") (pin "AN1") (pinfunction "1_AN1") (pintype "bidirectional"))
    )
    (net (code "442") (name "unconnected-(U$10X-1-PadAN2)") (class "Default")
      (node (ref "U$10") (pin "AN2") (pinfunction "1_AN2") (pintype "bidirectional"))
    )
    (net (code "443") (name "unconnected-(U$10Y-1-PadAP1)") (class "Default")
      (node (ref "U$10") (pin "AP1") (pinfunction "1_AP1") (pintype "bidirectional"))
    )
    (net (code "444") (name "unconnected-(U$10Z-1-PadAP2)") (class "Default")
      (node (ref "U$10") (pin "AP2") (pinfunction "1_AP2") (pintype "bidirectional"))
    )
  )
)
